# temperture.net
KiCad netlist of a schematic drawn in Altium Designer
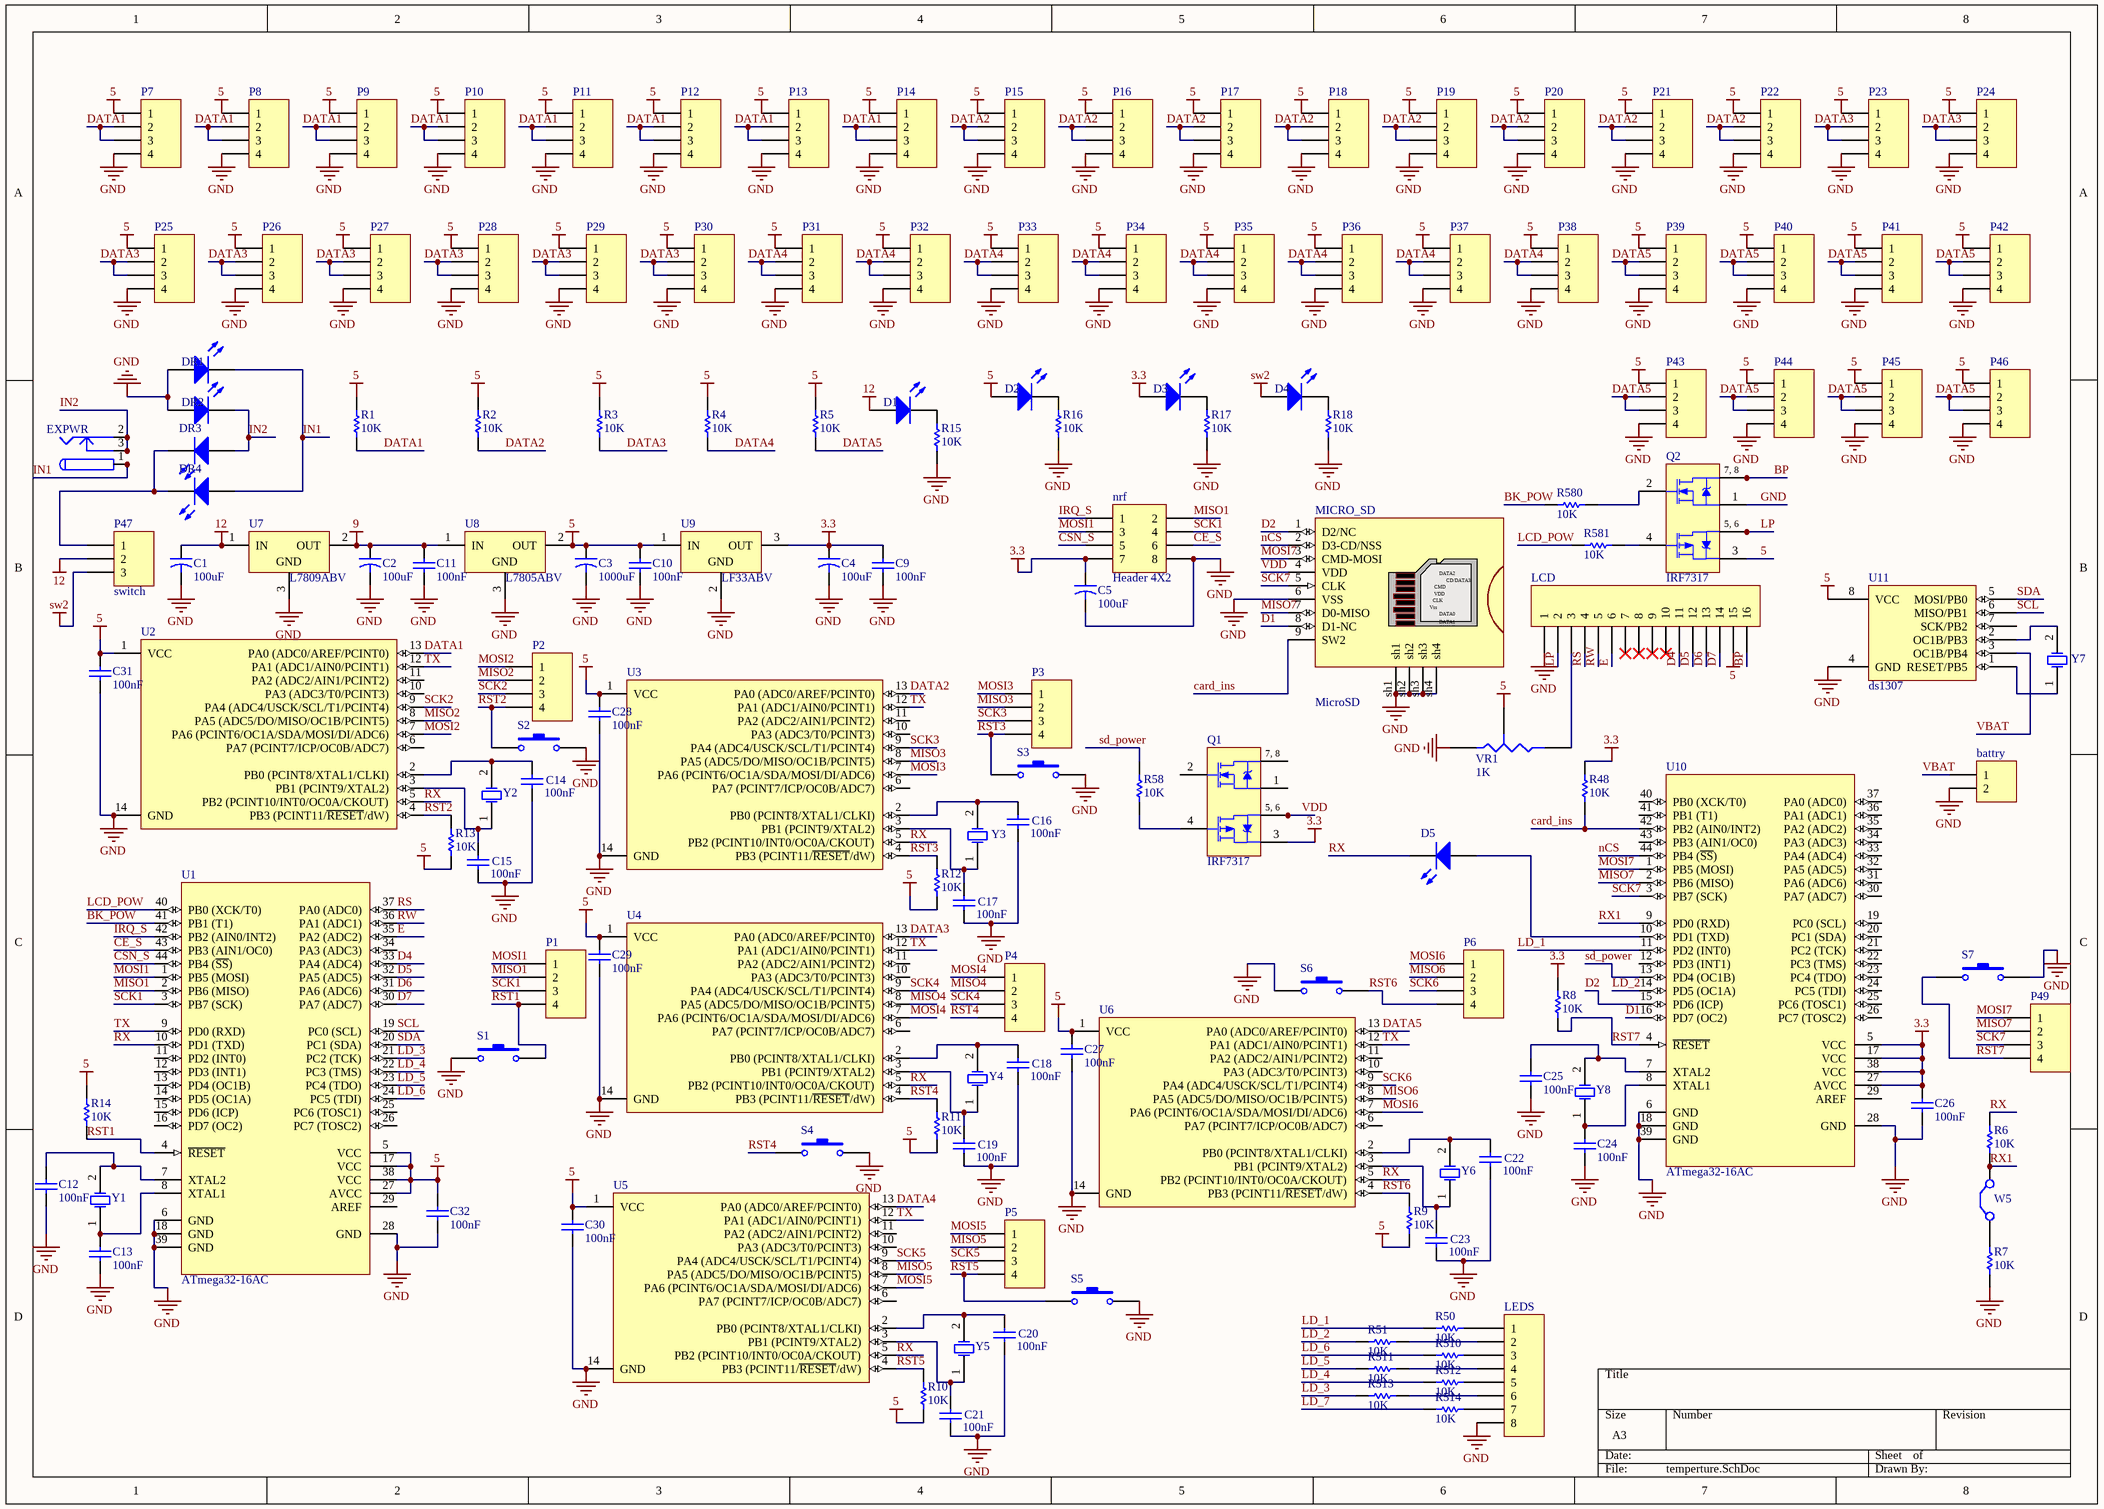
[diagram p0: temperture.SchDoc]

(export (version "E")
  (design (tool "Eeschema 10.0.6"))
  (components
    (comp (ref "battry")
      (value "Header 2")
      (footprint "Ultimate PCB Footprint:Battry")
      (description "Header, 2-Pin")
      (fields (field (name "PUBLISHER") "Altium Limited"))
      (libsource (lib "Miscellaneous Connectors") (part "Header 2"))
    )
    (comp (ref "C1")
      (value "100uF")
      (footprint "cap")
      (description "Capacitor")
      (fields (field (name "Comment") "Cap2") (field (name "PUBLISHER") "Altium Limited"))
      (libsource (lib "Miscellaneous Devices") (part "Cap2"))
    )
    (comp (ref "C2")
      (value "100uF")
      (footprint "cap")
      (description "Capacitor")
      (fields (field (name "Comment") "Cap2") (field (name "PUBLISHER") "Altium Limited"))
      (libsource (lib "Miscellaneous Devices") (part "Cap2"))
    )
    (comp (ref "C3")
      (value "1000uF")
      (footprint "cap")
      (description "Capacitor")
      (fields (field (name "Comment") "Cap2") (field (name "PUBLISHER") "Altium Limited"))
      (libsource (lib "Miscellaneous Devices") (part "Cap2"))
    )
    (comp (ref "C4")
      (value "100uF")
      (footprint "cap")
      (description "Capacitor")
      (fields (field (name "Comment") "Cap2") (field (name "PUBLISHER") "Altium Limited"))
      (libsource (lib "Miscellaneous Devices") (part "Cap2"))
    )
    (comp (ref "C5")
      (value "100uF")
      (footprint "cap")
      (description "Capacitor")
      (fields (field (name "Comment") "Cap2") (field (name "PUBLISHER") "Altium Limited"))
      (libsource (lib "Miscellaneous Devices") (part "Cap2"))
    )
    (comp (ref "C9")
      (value "100nF")
      (footprint "H1X02F")
      (description "Capacitor")
      (fields (field (name "Comment") "Cap") (field (name "PUBLISHER") "Altium Limited"))
      (libsource (lib "Miscellaneous Devices") (part "Cap"))
    )
    (comp (ref "C10")
      (value "100nF")
      (footprint "H1X02F")
      (description "Capacitor")
      (fields (field (name "Comment") "Cap") (field (name "PUBLISHER") "Altium Limited"))
      (libsource (lib "Miscellaneous Devices") (part "Cap"))
    )
    (comp (ref "C11")
      (value "100nF")
      (footprint "H1X02F")
      (description "Capacitor")
      (fields (field (name "Comment") "Cap") (field (name "PUBLISHER") "Altium Limited"))
      (libsource (lib "Miscellaneous Devices") (part "Cap"))
    )
    (comp (ref "C12")
      (value "100nF")
      (footprint "H1X02F")
      (description "Capacitor")
      (fields (field (name "Comment") "Cap") (field (name "PUBLISHER") "Altium Limited"))
      (libsource (lib "Miscellaneous Devices") (part "Cap"))
    )
    (comp (ref "C13")
      (value "100nF")
      (footprint "H1X02F")
      (description "Capacitor")
      (fields (field (name "Comment") "Cap") (field (name "PUBLISHER") "Altium Limited"))
      (libsource (lib "Miscellaneous Devices") (part "Cap"))
    )
    (comp (ref "C14")
      (value "100nF")
      (footprint "H1X02F")
      (description "Capacitor")
      (fields (field (name "Comment") "Cap") (field (name "PUBLISHER") "Altium Limited"))
      (libsource (lib "Miscellaneous Devices") (part "Cap"))
    )
    (comp (ref "C15")
      (value "100nF")
      (footprint "H1X02F")
      (description "Capacitor")
      (fields (field (name "Comment") "Cap") (field (name "PUBLISHER") "Altium Limited"))
      (libsource (lib "Miscellaneous Devices") (part "Cap"))
    )
    (comp (ref "C16")
      (value "100nF")
      (footprint "H1X02F")
      (description "Capacitor")
      (fields (field (name "Comment") "Cap") (field (name "PUBLISHER") "Altium Limited"))
      (libsource (lib "Miscellaneous Devices") (part "Cap"))
    )
    (comp (ref "C17")
      (value "100nF")
      (footprint "H1X02F")
      (description "Capacitor")
      (fields (field (name "Comment") "Cap") (field (name "PUBLISHER") "Altium Limited"))
      (libsource (lib "Miscellaneous Devices") (part "Cap"))
    )
    (comp (ref "C18")
      (value "100nF")
      (footprint "H1X02F")
      (description "Capacitor")
      (fields (field (name "Comment") "Cap") (field (name "PUBLISHER") "Altium Limited"))
      (libsource (lib "Miscellaneous Devices") (part "Cap"))
    )
    (comp (ref "C19")
      (value "100nF")
      (footprint "H1X02F")
      (description "Capacitor")
      (fields (field (name "Comment") "Cap") (field (name "PUBLISHER") "Altium Limited"))
      (libsource (lib "Miscellaneous Devices") (part "Cap"))
    )
    (comp (ref "C20")
      (value "100nF")
      (footprint "H1X02F")
      (description "Capacitor")
      (fields (field (name "Comment") "Cap") (field (name "PUBLISHER") "Altium Limited"))
      (libsource (lib "Miscellaneous Devices") (part "Cap"))
    )
    (comp (ref "C21")
      (value "100nF")
      (footprint "H1X02F")
      (description "Capacitor")
      (fields (field (name "Comment") "Cap") (field (name "PUBLISHER") "Altium Limited"))
      (libsource (lib "Miscellaneous Devices") (part "Cap"))
    )
    (comp (ref "C22")
      (value "100nF")
      (footprint "H1X02F")
      (description "Capacitor")
      (fields (field (name "Comment") "Cap") (field (name "PUBLISHER") "Altium Limited"))
      (libsource (lib "Miscellaneous Devices") (part "Cap"))
    )
    (comp (ref "C23")
      (value "100nF")
      (footprint "H1X02F")
      (description "Capacitor")
      (fields (field (name "Comment") "Cap") (field (name "PUBLISHER") "Altium Limited"))
      (libsource (lib "Miscellaneous Devices") (part "Cap"))
    )
    (comp (ref "C24")
      (value "100nF")
      (footprint "H1X02F")
      (description "Capacitor")
      (fields (field (name "Comment") "Cap") (field (name "PUBLISHER") "Altium Limited"))
      (libsource (lib "Miscellaneous Devices") (part "Cap"))
    )
    (comp (ref "C25")
      (value "100nF")
      (footprint "H1X02F")
      (description "Capacitor")
      (fields (field (name "Comment") "Cap") (field (name "PUBLISHER") "Altium Limited"))
      (libsource (lib "Miscellaneous Devices") (part "Cap"))
    )
    (comp (ref "C26")
      (value "100nF")
      (footprint "H1X02F")
      (description "Capacitor")
      (fields (field (name "Comment") "Cap") (field (name "PUBLISHER") "Altium Limited"))
      (libsource (lib "Miscellaneous Devices") (part "Cap"))
    )
    (comp (ref "C27")
      (value "100nF")
      (footprint "H1X02F")
      (description "Capacitor")
      (fields (field (name "Comment") "Cap") (field (name "PUBLISHER") "Altium Limited"))
      (libsource (lib "Miscellaneous Devices") (part "Cap"))
    )
    (comp (ref "C28")
      (value "100nF")
      (footprint "H1X02F")
      (description "Capacitor")
      (fields (field (name "Comment") "Cap") (field (name "PUBLISHER") "Altium Limited"))
      (libsource (lib "Miscellaneous Devices") (part "Cap"))
    )
    (comp (ref "C29")
      (value "100nF")
      (footprint "H1X02F")
      (description "Capacitor")
      (fields (field (name "Comment") "Cap") (field (name "PUBLISHER") "Altium Limited"))
      (libsource (lib "Miscellaneous Devices") (part "Cap"))
    )
    (comp (ref "C30")
      (value "100nF")
      (footprint "H1X02F")
      (description "Capacitor")
      (fields (field (name "Comment") "Cap") (field (name "PUBLISHER") "Altium Limited"))
      (libsource (lib "Miscellaneous Devices") (part "Cap"))
    )
    (comp (ref "C31")
      (value "100nF")
      (footprint "H1X02F")
      (description "Capacitor")
      (fields (field (name "Comment") "Cap") (field (name "PUBLISHER") "Altium Limited"))
      (libsource (lib "Miscellaneous Devices") (part "Cap"))
    )
    (comp (ref "C32")
      (value "100nF")
      (footprint "H1X02F")
      (description "Capacitor")
      (fields (field (name "Comment") "Cap") (field (name "PUBLISHER") "Altium Limited"))
      (libsource (lib "Miscellaneous Devices") (part "Cap"))
    )
    (comp (ref "D1")
      (value "LED0")
      (footprint "LED5mm")
      (description "Typical INFRARED GaAs LED")
      (fields (field (name "PUBLISHER") "Altium Limited"))
      (libsource (lib "Miscellaneous Devices") (part "LED0"))
    )
    (comp (ref "D2")
      (value "LED0")
      (footprint "LED5mm")
      (description "Typical INFRARED GaAs LED")
      (fields (field (name "PUBLISHER") "Altium Limited"))
      (libsource (lib "Miscellaneous Devices") (part "LED0"))
    )
    (comp (ref "D3")
      (value "LED0")
      (footprint "LED5mm")
      (description "Typical INFRARED GaAs LED")
      (fields (field (name "PUBLISHER") "Altium Limited"))
      (libsource (lib "Miscellaneous Devices") (part "LED0"))
    )
    (comp (ref "D4")
      (value "LED0")
      (footprint "LED5mm")
      (description "Typical INFRARED GaAs LED")
      (fields (field (name "PUBLISHER") "Altium Limited"))
      (libsource (lib "Miscellaneous Devices") (part "LED0"))
    )
    (comp (ref "D5")
      (value "LED0")
      (footprint "AXIAL-0.4")
      (description "Typical INFRARED GaAs LED")
      (fields (field (name "PUBLISHER") "Altium Limited"))
      (libsource (lib "Miscellaneous Devices") (part "LED0"))
    )
    (comp (ref "DR1")
      (value "LED0")
      (footprint "AXIAL-0.3")
      (description "Typical INFRARED GaAs LED")
      (fields (field (name "PUBLISHER") "Altium Limited"))
      (libsource (lib "Miscellaneous Devices") (part "LED0"))
    )
    (comp (ref "DR2")
      (value "LED0")
      (footprint "AXIAL-0.3")
      (description "Typical INFRARED GaAs LED")
      (fields (field (name "PUBLISHER") "Altium Limited"))
      (libsource (lib "Miscellaneous Devices") (part "LED0"))
    )
    (comp (ref "DR3")
      (value "LED0")
      (footprint "AXIAL-0.3")
      (description "Typical INFRARED GaAs LED")
      (fields (field (name "PUBLISHER") "Altium Limited"))
      (libsource (lib "Miscellaneous Devices") (part "LED0"))
    )
    (comp (ref "DR4")
      (value "LED0")
      (footprint "AXIAL-0.3")
      (description "Typical INFRARED GaAs LED")
      (fields (field (name "PUBLISHER") "Altium Limited"))
      (libsource (lib "Miscellaneous Devices") (part "LED0"))
    )
    (comp (ref "EXPWR")
      (value "PWR2.5")
      (footprint "JACK1")
      (description "Low Voltage Power Supply Connector")
      (fields (field (name "PUBLISHER") "Altium Limited"))
      (libsource (lib "Miscellaneous Connectors") (part "PWR2.5"))
    )
    (comp (ref "LCD")
      (value "Header 16")
      (footprint "H1X16F")
      (description "Header, 16-Pin")
      (fields (field (name "PUBLISHER") "Altium Limited"))
      (libsource (lib "Miscellaneous Connectors") (part "Header 16"))
    )
    (comp (ref "LEDS")
      (value "Header 8")
      (footprint "H1X08F")
      (description "Header, 8-Pin")
      (fields (field (name "PUBLISHER") "Altium Limited"))
      (libsource (lib "Miscellaneous Connectors") (part "Header 8"))
    )
    (comp (ref "MICRO_SD")
      (value "MicroSD")
      (footprint "MicroSD_1")
      (description "MicroSD_altium designer (M.Hariri)")
      (fields (field (name "CREATED BY:") "*"))
      (libsource (lib "MicroSD_altium designer") (part "MicroSD"))
    )
    (comp (ref "nrf")
      (value "Header 4X2")
      (footprint "HDR2X4")
      (description "Header, 4-Pin, Dual row")
      (fields (field (name "PUBLISHER") "Altium Limited"))
      (libsource (lib "Miscellaneous Connectors") (part "Header 4X2"))
    )
    (comp (ref "P1")
      (value "Header 4")
      (footprint "H1X04F")
      (description "Header, 4-Pin")
      (fields (field (name "PUBLISHER") "Altium Limited"))
      (libsource (lib "Miscellaneous Connectors") (part "Header 4"))
    )
    (comp (ref "P2")
      (value "Header 4")
      (footprint "H1X04F")
      (description "Header, 4-Pin")
      (fields (field (name "PUBLISHER") "Altium Limited"))
      (libsource (lib "Miscellaneous Connectors") (part "Header 4"))
    )
    (comp (ref "P3")
      (value "Header 4")
      (footprint "H1X04F")
      (description "Header, 4-Pin")
      (fields (field (name "PUBLISHER") "Altium Limited"))
      (libsource (lib "Miscellaneous Connectors") (part "Header 4"))
    )
    (comp (ref "P4")
      (value "Header 4")
      (footprint "H1X04F")
      (description "Header, 4-Pin")
      (fields (field (name "PUBLISHER") "Altium Limited"))
      (libsource (lib "Miscellaneous Connectors") (part "Header 4"))
    )
    (comp (ref "P5")
      (value "Header 4")
      (footprint "H1X04F")
      (description "Header, 4-Pin")
      (fields (field (name "PUBLISHER") "Altium Limited"))
      (libsource (lib "Miscellaneous Connectors") (part "Header 4"))
    )
    (comp (ref "P6")
      (value "Header 4")
      (footprint "H1X04F")
      (description "Header, 4-Pin")
      (fields (field (name "PUBLISHER") "Altium Limited"))
      (libsource (lib "Miscellaneous Connectors") (part "Header 4"))
    )
    (comp (ref "P7")
      (value "Header 4")
      (footprint "RJ11")
      (description "Header, 4-Pin")
      (fields (field (name "PUBLISHER") "Altium Limited"))
      (libsource (lib "Miscellaneous Connectors") (part "Header 4"))
    )
    (comp (ref "P8")
      (value "Header 4")
      (footprint "RJ11")
      (description "Header, 4-Pin")
      (fields (field (name "PUBLISHER") "Altium Limited"))
      (libsource (lib "Miscellaneous Connectors") (part "Header 4"))
    )
    (comp (ref "P9")
      (value "Header 4")
      (footprint "RJ11")
      (description "Header, 4-Pin")
      (fields (field (name "PUBLISHER") "Altium Limited"))
      (libsource (lib "Miscellaneous Connectors") (part "Header 4"))
    )
    (comp (ref "P10")
      (value "Header 4")
      (footprint "RJ11")
      (description "Header, 4-Pin")
      (fields (field (name "PUBLISHER") "Altium Limited"))
      (libsource (lib "Miscellaneous Connectors") (part "Header 4"))
    )
    (comp (ref "P11")
      (value "Header 4")
      (footprint "RJ11")
      (description "Header, 4-Pin")
      (fields (field (name "PUBLISHER") "Altium Limited"))
      (libsource (lib "Miscellaneous Connectors") (part "Header 4"))
    )
    (comp (ref "P12")
      (value "Header 4")
      (footprint "RJ11")
      (description "Header, 4-Pin")
      (fields (field (name "PUBLISHER") "Altium Limited"))
      (libsource (lib "Miscellaneous Connectors") (part "Header 4"))
    )
    (comp (ref "P13")
      (value "Header 4")
      (footprint "RJ11")
      (description "Header, 4-Pin")
      (fields (field (name "PUBLISHER") "Altium Limited"))
      (libsource (lib "Miscellaneous Connectors") (part "Header 4"))
    )
    (comp (ref "P14")
      (value "Header 4")
      (footprint "RJ11")
      (description "Header, 4-Pin")
      (fields (field (name "PUBLISHER") "Altium Limited"))
      (libsource (lib "Miscellaneous Connectors") (part "Header 4"))
    )
    (comp (ref "P15")
      (value "Header 4")
      (footprint "RJ11")
      (description "Header, 4-Pin")
      (fields (field (name "PUBLISHER") "Altium Limited"))
      (libsource (lib "Miscellaneous Connectors") (part "Header 4"))
    )
    (comp (ref "P16")
      (value "Header 4")
      (footprint "RJ11")
      (description "Header, 4-Pin")
      (fields (field (name "PUBLISHER") "Altium Limited"))
      (libsource (lib "Miscellaneous Connectors") (part "Header 4"))
    )
    (comp (ref "P17")
      (value "Header 4")
      (footprint "RJ11")
      (description "Header, 4-Pin")
      (fields (field (name "PUBLISHER") "Altium Limited"))
      (libsource (lib "Miscellaneous Connectors") (part "Header 4"))
    )
    (comp (ref "P18")
      (value "Header 4")
      (footprint "RJ11")
      (description "Header, 4-Pin")
      (fields (field (name "PUBLISHER") "Altium Limited"))
      (libsource (lib "Miscellaneous Connectors") (part "Header 4"))
    )
    (comp (ref "P19")
      (value "Header 4")
      (footprint "RJ11")
      (description "Header, 4-Pin")
      (fields (field (name "PUBLISHER") "Altium Limited"))
      (libsource (lib "Miscellaneous Connectors") (part "Header 4"))
    )
    (comp (ref "P20")
      (value "Header 4")
      (footprint "RJ11")
      (description "Header, 4-Pin")
      (fields (field (name "PUBLISHER") "Altium Limited"))
      (libsource (lib "Miscellaneous Connectors") (part "Header 4"))
    )
    (comp (ref "P21")
      (value "Header 4")
      (footprint "RJ11")
      (description "Header, 4-Pin")
      (fields (field (name "PUBLISHER") "Altium Limited"))
      (libsource (lib "Miscellaneous Connectors") (part "Header 4"))
    )
    (comp (ref "P22")
      (value "Header 4")
      (footprint "RJ11")
      (description "Header, 4-Pin")
      (fields (field (name "PUBLISHER") "Altium Limited"))
      (libsource (lib "Miscellaneous Connectors") (part "Header 4"))
    )
    (comp (ref "P23")
      (value "Header 4")
      (footprint "RJ11")
      (description "Header, 4-Pin")
      (fields (field (name "PUBLISHER") "Altium Limited"))
      (libsource (lib "Miscellaneous Connectors") (part "Header 4"))
    )
    (comp (ref "P24")
      (value "Header 4")
      (footprint "RJ11")
      (description "Header, 4-Pin")
      (fields (field (name "PUBLISHER") "Altium Limited"))
      (libsource (lib "Miscellaneous Connectors") (part "Header 4"))
    )
    (comp (ref "P25")
      (value "Header 4")
      (footprint "RJ11")
      (description "Header, 4-Pin")
      (fields (field (name "PUBLISHER") "Altium Limited"))
      (libsource (lib "Miscellaneous Connectors") (part "Header 4"))
    )
    (comp (ref "P26")
      (value "Header 4")
      (footprint "RJ11")
      (description "Header, 4-Pin")
      (fields (field (name "PUBLISHER") "Altium Limited"))
      (libsource (lib "Miscellaneous Connectors") (part "Header 4"))
    )
    (comp (ref "P27")
      (value "Header 4")
      (footprint "RJ11")
      (description "Header, 4-Pin")
      (fields (field (name "PUBLISHER") "Altium Limited"))
      (libsource (lib "Miscellaneous Connectors") (part "Header 4"))
    )
    (comp (ref "P28")
      (value "Header 4")
      (footprint "RJ11")
      (description "Header, 4-Pin")
      (fields (field (name "PUBLISHER") "Altium Limited"))
      (libsource (lib "Miscellaneous Connectors") (part "Header 4"))
    )
    (comp (ref "P29")
      (value "Header 4")
      (footprint "RJ11")
      (description "Header, 4-Pin")
      (fields (field (name "PUBLISHER") "Altium Limited"))
      (libsource (lib "Miscellaneous Connectors") (part "Header 4"))
    )
    (comp (ref "P30")
      (value "Header 4")
      (footprint "RJ11")
      (description "Header, 4-Pin")
      (fields (field (name "PUBLISHER") "Altium Limited"))
      (libsource (lib "Miscellaneous Connectors") (part "Header 4"))
    )
    (comp (ref "P31")
      (value "Header 4")
      (footprint "RJ11")
      (description "Header, 4-Pin")
      (fields (field (name "PUBLISHER") "Altium Limited"))
      (libsource (lib "Miscellaneous Connectors") (part "Header 4"))
    )
    (comp (ref "P32")
      (value "Header 4")
      (footprint "RJ11")
      (description "Header, 4-Pin")
      (fields (field (name "PUBLISHER") "Altium Limited"))
      (libsource (lib "Miscellaneous Connectors") (part "Header 4"))
    )
    (comp (ref "P33")
      (value "Header 4")
      (footprint "RJ11")
      (description "Header, 4-Pin")
      (fields (field (name "PUBLISHER") "Altium Limited"))
      (libsource (lib "Miscellaneous Connectors") (part "Header 4"))
    )
    (comp (ref "P34")
      (value "Header 4")
      (footprint "RJ11")
      (description "Header, 4-Pin")
      (fields (field (name "PUBLISHER") "Altium Limited"))
      (libsource (lib "Miscellaneous Connectors") (part "Header 4"))
    )
    (comp (ref "P35")
      (value "Header 4")
      (footprint "RJ11")
      (description "Header, 4-Pin")
      (fields (field (name "PUBLISHER") "Altium Limited"))
      (libsource (lib "Miscellaneous Connectors") (part "Header 4"))
    )
    (comp (ref "P36")
      (value "Header 4")
      (footprint "RJ11")
      (description "Header, 4-Pin")
      (fields (field (name "PUBLISHER") "Altium Limited"))
      (libsource (lib "Miscellaneous Connectors") (part "Header 4"))
    )
    (comp (ref "P37")
      (value "Header 4")
      (footprint "RJ11")
      (description "Header, 4-Pin")
      (fields (field (name "PUBLISHER") "Altium Limited"))
      (libsource (lib "Miscellaneous Connectors") (part "Header 4"))
    )
    (comp (ref "P38")
      (value "Header 4")
      (footprint "RJ11")
      (description "Header, 4-Pin")
      (fields (field (name "PUBLISHER") "Altium Limited"))
      (libsource (lib "Miscellaneous Connectors") (part "Header 4"))
    )
    (comp (ref "P39")
      (value "Header 4")
      (footprint "RJ11")
      (description "Header, 4-Pin")
      (fields (field (name "PUBLISHER") "Altium Limited"))
      (libsource (lib "Miscellaneous Connectors") (part "Header 4"))
    )
    (comp (ref "P40")
      (value "Header 4")
      (footprint "RJ11")
      (description "Header, 4-Pin")
      (fields (field (name "PUBLISHER") "Altium Limited"))
      (libsource (lib "Miscellaneous Connectors") (part "Header 4"))
    )
    (comp (ref "P41")
      (value "Header 4")
      (footprint "RJ11")
      (description "Header, 4-Pin")
      (fields (field (name "PUBLISHER") "Altium Limited"))
      (libsource (lib "Miscellaneous Connectors") (part "Header 4"))
    )
    (comp (ref "P42")
      (value "Header 4")
      (footprint "RJ11")
      (description "Header, 4-Pin")
      (fields (field (name "PUBLISHER") "Altium Limited"))
      (libsource (lib "Miscellaneous Connectors") (part "Header 4"))
    )
    (comp (ref "P43")
      (value "Header 4")
      (footprint "RJ11")
      (description "Header, 4-Pin")
      (fields (field (name "PUBLISHER") "Altium Limited"))
      (libsource (lib "Miscellaneous Connectors") (part "Header 4"))
    )
    (comp (ref "P44")
      (value "Header 4")
      (footprint "RJ11")
      (description "Header, 4-Pin")
      (fields (field (name "PUBLISHER") "Altium Limited"))
      (libsource (lib "Miscellaneous Connectors") (part "Header 4"))
    )
    (comp (ref "P45")
      (value "Header 4")
      (footprint "RJ11")
      (description "Header, 4-Pin")
      (fields (field (name "PUBLISHER") "Altium Limited"))
      (libsource (lib "Miscellaneous Connectors") (part "Header 4"))
    )
    (comp (ref "P46")
      (value "Header 4")
      (footprint "RJ11")
      (description "Header, 4-Pin")
      (fields (field (name "PUBLISHER") "Altium Limited"))
      (libsource (lib "Miscellaneous Connectors") (part "Header 4"))
    )
    (comp (ref "P47")
      (value "switch")
      (footprint "peymanswitch")
      (description "Header, 3-Pin")
      (fields (field (name "PUBLISHER") "Altium Limited"))
      (libsource (lib "Miscellaneous Connectors") (part "Header 3"))
    )
    (comp (ref "P49")
      (value "Header 4")
      (footprint "H1X04F")
      (description "Header, 4-Pin")
      (fields (field (name "PUBLISHER") "Altium Limited"))
      (libsource (lib "Miscellaneous Connectors") (part "Header 4"))
    )
    (comp (ref "Q1")
      (value "IRF7317")
      (footprint "SO-8_N")
      (description "HEXFET Power MOSFET")
      (fields (field (name "PUBLISHER") "Altium Limited"))
      (libsource (lib "IR Discrete MOSFET - Power") (part "IRF7317"))
    )
    (comp (ref "Q2")
      (value "IRF7317")
      (footprint "International Rectifier Footprints:SO-8_N")
      (description "HEXFET Power MOSFET")
      (fields (field (name "PUBLISHER") "Altium Limited"))
      (libsource (lib "IR Discrete MOSFET - Power") (part "IRF7317"))
    )
    (comp (ref "R1")
      (value "10K")
      (footprint "AXIAL-0.3")
      (description "Resistor")
      (fields (field (name "Comment") "Res1") (field (name "PUBLISHER") "Altium Limited"))
      (libsource (lib "Miscellaneous Devices") (part "Res1"))
    )
    (comp (ref "R2")
      (value "10K")
      (footprint "AXIAL-0.3")
      (description "Resistor")
      (fields (field (name "Comment") "Res1") (field (name "PUBLISHER") "Altium Limited"))
      (libsource (lib "Miscellaneous Devices") (part "Res1"))
    )
    (comp (ref "R3")
      (value "10K")
      (footprint "AXIAL-0.3")
      (description "Resistor")
      (fields (field (name "Comment") "Res1") (field (name "PUBLISHER") "Altium Limited"))
      (libsource (lib "Miscellaneous Devices") (part "Res1"))
    )
    (comp (ref "R4")
      (value "10K")
      (footprint "AXIAL-0.3")
      (description "Resistor")
      (fields (field (name "Comment") "Res1") (field (name "PUBLISHER") "Altium Limited"))
      (libsource (lib "Miscellaneous Devices") (part "Res1"))
    )
    (comp (ref "R5")
      (value "10K")
      (footprint "AXIAL-0.3")
      (description "Resistor")
      (fields (field (name "Comment") "Res1") (field (name "PUBLISHER") "Altium Limited"))
      (libsource (lib "Miscellaneous Devices") (part "Res1"))
    )
    (comp (ref "R6")
      (value "10K")
      (footprint "AXIAL-0.3")
      (description "Resistor")
      (fields (field (name "Comment") "Res1") (field (name "PUBLISHER") "Altium Limited"))
      (libsource (lib "Miscellaneous Devices") (part "Res1"))
    )
    (comp (ref "R7")
      (value "10K")
      (footprint "AXIAL-0.3")
      (description "Resistor")
      (fields (field (name "Comment") "Res1") (field (name "PUBLISHER") "Altium Limited"))
      (libsource (lib "Miscellaneous Devices") (part "Res1"))
    )
    (comp (ref "R8")
      (value "10K")
      (footprint "AXIAL-0.3")
      (description "Resistor")
      (fields (field (name "Comment") "Res1") (field (name "PUBLISHER") "Altium Limited"))
      (libsource (lib "Miscellaneous Devices") (part "Res1"))
    )
    (comp (ref "R9")
      (value "10K")
      (footprint "AXIAL-0.3")
      (description "Resistor")
      (fields (field (name "Comment") "Res1") (field (name "PUBLISHER") "Altium Limited"))
      (libsource (lib "Miscellaneous Devices") (part "Res1"))
    )
    (comp (ref "R10")
      (value "10K")
      (footprint "AXIAL-0.3")
      (description "Resistor")
      (fields (field (name "Comment") "Res1") (field (name "PUBLISHER") "Altium Limited"))
      (libsource (lib "Miscellaneous Devices") (part "Res1"))
    )
    (comp (ref "R11")
      (value "10K")
      (footprint "AXIAL-0.3")
      (description "Resistor")
      (fields (field (name "Comment") "Res1") (field (name "PUBLISHER") "Altium Limited"))
      (libsource (lib "Miscellaneous Devices") (part "Res1"))
    )
    (comp (ref "R12")
      (value "10K")
      (footprint "AXIAL-0.3")
      (description "Resistor")
      (fields (field (name "Comment") "Res1") (field (name "PUBLISHER") "Altium Limited"))
      (libsource (lib "Miscellaneous Devices") (part "Res1"))
    )
    (comp (ref "R13")
      (value "10K")
      (footprint "AXIAL-0.3")
      (description "Resistor")
      (fields (field (name "Comment") "Res1") (field (name "PUBLISHER") "Altium Limited"))
      (libsource (lib "Miscellaneous Devices") (part "Res1"))
    )
    (comp (ref "R14")
      (value "10K")
      (footprint "AXIAL-0.3")
      (description "Resistor")
      (fields (field (name "Comment") "Res1") (field (name "PUBLISHER") "Altium Limited"))
      (libsource (lib "Miscellaneous Devices") (part "Res1"))
    )
    (comp (ref "R15")
      (value "10K")
      (footprint "AXIAL-0.3")
      (description "Resistor")
      (fields (field (name "Comment") "Res1") (field (name "PUBLISHER") "Altium Limited"))
      (libsource (lib "Miscellaneous Devices") (part "Res1"))
    )
    (comp (ref "R16")
      (value "10K")
      (footprint "AXIAL-0.3")
      (description "Resistor")
      (fields (field (name "Comment") "Res1") (field (name "PUBLISHER") "Altium Limited"))
      (libsource (lib "Miscellaneous Devices") (part "Res1"))
    )
    (comp (ref "R17")
      (value "10K")
      (footprint "AXIAL-0.3")
      (description "Resistor")
      (fields (field (name "Comment") "Res1") (field (name "PUBLISHER") "Altium Limited"))
      (libsource (lib "Miscellaneous Devices") (part "Res1"))
    )
    (comp (ref "R18")
      (value "10K")
      (footprint "AXIAL-0.3")
      (description "Resistor")
      (fields (field (name "Comment") "Res1") (field (name "PUBLISHER") "Altium Limited"))
      (libsource (lib "Miscellaneous Devices") (part "Res1"))
    )
    (comp (ref "R48")
      (value "10K")
      (footprint "AXIAL-0.3")
      (description "Resistor")
      (fields (field (name "Comment") "Res1") (field (name "PUBLISHER") "Altium Limited"))
      (libsource (lib "Miscellaneous Devices") (part "Res1"))
    )
    (comp (ref "R50")
      (value "10K")
      (footprint "AXIAL-0.3")
      (description "Resistor")
      (fields (field (name "Comment") "Res1") (field (name "PUBLISHER") "Altium Limited"))
      (libsource (lib "Miscellaneous Devices") (part "Res1"))
    )
    (comp (ref "R51")
      (value "10K")
      (footprint "AXIAL-0.3")
      (description "Resistor")
      (fields (field (name "Comment") "Res1") (field (name "PUBLISHER") "Altium Limited"))
      (libsource (lib "Miscellaneous Devices") (part "Res1"))
    )
    (comp (ref "R58")
      (value "10K")
      (footprint "AXIAL-0.3")
      (description "Resistor")
      (fields (field (name "Comment") "Res1") (field (name "PUBLISHER") "Altium Limited"))
      (libsource (lib "Miscellaneous Devices") (part "Res1"))
    )
    (comp (ref "R510")
      (value "10K")
      (footprint "SMD[1206]")
      (description "Resistor")
      (fields (field (name "Comment") "Res1") (field (name "PUBLISHER") "Altium Limited"))
      (libsource (lib "Miscellaneous Devices") (part "Res1"))
    )
    (comp (ref "R511")
      (value "10K")
      (footprint "SMD[1206]")
      (description "Resistor")
      (fields (field (name "Comment") "Res1") (field (name "PUBLISHER") "Altium Limited"))
      (libsource (lib "Miscellaneous Devices") (part "Res1"))
    )
    (comp (ref "R512")
      (value "10K")
      (footprint "SMD[1206]")
      (description "Resistor")
      (fields (field (name "Comment") "Res1") (field (name "PUBLISHER") "Altium Limited"))
      (libsource (lib "Miscellaneous Devices") (part "Res1"))
    )
    (comp (ref "R513")
      (value "10K")
      (footprint "SMD[1206]")
      (description "Resistor")
      (fields (field (name "Comment") "Res1") (field (name "PUBLISHER") "Altium Limited"))
      (libsource (lib "Miscellaneous Devices") (part "Res1"))
    )
    (comp (ref "R514")
      (value "10K")
      (footprint "SMD[1206]")
      (description "Resistor")
      (fields (field (name "Comment") "Res1") (field (name "PUBLISHER") "Altium Limited"))
      (libsource (lib "Miscellaneous Devices") (part "Res1"))
    )
    (comp (ref "R580")
      (value "10K")
      (footprint "AXIAL-0.3")
      (description "Resistor")
      (fields (field (name "Comment") "Res1") (field (name "PUBLISHER") "Altium Limited"))
      (libsource (lib "Miscellaneous Devices") (part "Res1"))
    )
    (comp (ref "R581")
      (value "10K")
      (footprint "AXIAL-0.3")
      (description "Resistor")
      (fields (field (name "Comment") "Res1") (field (name "PUBLISHER") "Altium Limited"))
      (libsource (lib "Miscellaneous Devices") (part "Res1"))
    )
    (comp (ref "S1")
      (value "SW-PB")
      (footprint "PB4")
      (description "Switch")
      (fields (field (name "PUBLISHER") "Altium Limited"))
      (libsource (lib "Miscellaneous Devices") (part "SW-PB"))
    )
    (comp (ref "S2")
      (value "SW-PB")
      (footprint "PB4")
      (description "Switch")
      (fields (field (name "PUBLISHER") "Altium Limited"))
      (libsource (lib "Miscellaneous Devices") (part "SW-PB"))
    )
    (comp (ref "S3")
      (value "SW-PB")
      (footprint "PB4")
      (description "Switch")
      (fields (field (name "PUBLISHER") "Altium Limited"))
      (libsource (lib "Miscellaneous Devices") (part "SW-PB"))
    )
    (comp (ref "S4")
      (value "SW-PB")
      (footprint "PB4")
      (description "Switch")
      (fields (field (name "PUBLISHER") "Altium Limited"))
      (libsource (lib "Miscellaneous Devices") (part "SW-PB"))
    )
    (comp (ref "S5")
      (value "SW-PB")
      (footprint "PB4")
      (description "Switch")
      (fields (field (name "PUBLISHER") "Altium Limited"))
      (libsource (lib "Miscellaneous Devices") (part "SW-PB"))
    )
    (comp (ref "S6")
      (value "SW-PB")
      (footprint "PB4")
      (description "Switch")
      (fields (field (name "PUBLISHER") "Altium Limited"))
      (libsource (lib "Miscellaneous Devices") (part "SW-PB"))
    )
    (comp (ref "S7")
      (value "SW-PB")
      (footprint "PB4")
      (description "Switch")
      (fields (field (name "PUBLISHER") "Altium Limited"))
      (libsource (lib "Miscellaneous Devices") (part "SW-PB"))
    )
    (comp (ref "U1")
      (value "ATmega32-16AC")
      (footprint "TQFP44")
      (description "8-Bit AVR Microcontroller with 32K Bytes of In-System Programmable Flash Memory")
      (fields (field (name "PUBLISHER") "Altium Limited"))
      (libsource (lib "Atmel Microcontroller 8-Bit AVR") (part "ATmega32-16AC"))
    )
    (comp (ref "U2")
      (value "ATtiny24V-10SSU")
      (footprint "SOIC14")
      (fields (field (name "PUBLISHER") "Altium Limited"))
      (libsource (lib "Atmel Microcontroller 8-Bit tinyAVR") (part "ATtiny24V-10SSU"))
    )
    (comp (ref "U3")
      (value "ATtiny24V-10SSU")
      (footprint "SOIC14")
      (fields (field (name "PUBLISHER") "Altium Limited"))
      (libsource (lib "Atmel Microcontroller 8-Bit tinyAVR") (part "ATtiny24V-10SSU"))
    )
    (comp (ref "U4")
      (value "ATtiny24V-10SSU")
      (footprint "SOIC14")
      (fields (field (name "PUBLISHER") "Altium Limited"))
      (libsource (lib "Atmel Microcontroller 8-Bit tinyAVR") (part "ATtiny24V-10SSU"))
    )
    (comp (ref "U5")
      (value "ATtiny24V-10SSU")
      (footprint "SOIC14")
      (fields (field (name "PUBLISHER") "Altium Limited"))
      (libsource (lib "Atmel Microcontroller 8-Bit tinyAVR") (part "ATtiny24V-10SSU"))
    )
    (comp (ref "U6")
      (value "ATtiny24V-10SSU")
      (footprint "SOIC14")
      (fields (field (name "PUBLISHER") "Altium Limited"))
      (libsource (lib "Atmel Microcontroller 8-Bit tinyAVR") (part "ATtiny24V-10SSU"))
    )
    (comp (ref "U7")
      (value "L7809ABV")
      (footprint "TO220ABN")
      (description "Precision 1A Regulator")
      (fields (field (name "PUBLISHER") "Altium Limited"))
      (libsource (lib "ST Power Mgt Voltage Regulator") (part "L7809ABV"))
    )
    (comp (ref "U8")
      (value "L7805ABV")
      (footprint "TO220ABN")
      (description "Precision 1A Regulator")
      (fields (field (name "PUBLISHER") "Altium Limited"))
      (libsource (lib "ST Power Mgt Voltage Regulator") (part "L7805ABV"))
    )
    (comp (ref "U9")
      (value "LF33ABV")
      (footprint "TO-220A")
      (description "500mA, Very Low Drop (0.45V) Voltage Regulator")
      (fields (field (name "PUBLISHER") "Altium Limited"))
      (libsource (lib "ST Power Mgt Voltage Regulator") (part "LF33ABV"))
    )
    (comp (ref "U10")
      (value "ATmega32-16AC")
      (footprint "TQFP44")
      (description "8-Bit AVR Microcontroller with 32K Bytes of In-System Programmable Flash Memory")
      (fields (field (name "PUBLISHER") "Altium Limited"))
      (libsource (lib "Atmel Microcontroller 8-Bit AVR") (part "ATmega32-16AC"))
    )
    (comp (ref "U11")
      (value "ds1307")
      (footprint "DIP8-1")
      (description "Attiny45")
      (libsource (lib "Attiny85") (part "Attiny85"))
    )
    (comp (ref "VR1")
      (value "1K")
      (footprint "H1X03F")
      (description "Tapped Resistor")
      (fields (field (name "Comment") "Res Tap") (field (name "PUBLISHER") "Altium Limited"))
      (libsource (lib "Miscellaneous Devices") (part "Res Tap"))
    )
    (comp (ref "W5")
      (value "Jumper")
      (footprint "H1X02F")
      (description "Jumper Wire")
      (fields (field (name "PUBLISHER") "Altium Limited"))
      (libsource (lib "Miscellaneous Devices") (part "Jumper"))
    )
    (comp (ref "Y1")
      (value "XTAL")
      (footprint "CRYSTALL")
      (description "Crystal Oscillator")
      (fields (field (name "PUBLISHER") "Altium Limited"))
      (libsource (lib "Miscellaneous Devices") (part "XTAL"))
    )
    (comp (ref "Y2")
      (value "XTAL")
      (footprint "CRYSTALL")
      (description "Crystal Oscillator")
      (fields (field (name "PUBLISHER") "Altium Limited"))
      (libsource (lib "Miscellaneous Devices") (part "XTAL"))
    )
    (comp (ref "Y3")
      (value "XTAL")
      (footprint "CRYSTALL")
      (description "Crystal Oscillator")
      (fields (field (name "PUBLISHER") "Altium Limited"))
      (libsource (lib "Miscellaneous Devices") (part "XTAL"))
    )
    (comp (ref "Y4")
      (value "XTAL")
      (footprint "CRYSTALL")
      (description "Crystal Oscillator")
      (fields (field (name "PUBLISHER") "Altium Limited"))
      (libsource (lib "Miscellaneous Devices") (part "XTAL"))
    )
    (comp (ref "Y5")
      (value "XTAL")
      (footprint "CRYSTALL")
      (description "Crystal Oscillator")
      (fields (field (name "PUBLISHER") "Altium Limited"))
      (libsource (lib "Miscellaneous Devices") (part "XTAL"))
    )
    (comp (ref "Y6")
      (value "XTAL")
      (footprint "CRYSTALL")
      (description "Crystal Oscillator")
      (fields (field (name "PUBLISHER") "Altium Limited"))
      (libsource (lib "Miscellaneous Devices") (part "XTAL"))
    )
    (comp (ref "Y7")
      (value "XTAL")
      (footprint "H1X02F")
      (description "Crystal Oscillator")
      (fields (field (name "PUBLISHER") "Altium Limited"))
      (libsource (lib "Miscellaneous Devices") (part "XTAL"))
    )
    (comp (ref "Y8")
      (value "XTAL")
      (footprint "CRYSTALL")
      (description "Crystal Oscillator")
      (fields (field (name "PUBLISHER") "Altium Limited"))
      (libsource (lib "Miscellaneous Devices") (part "XTAL"))
    )
  )
  (nets
    (net (code "1") (name "/BK_POW") (class "Default")
      (node (ref "R580") (pin "1") (pinfunction "1_1") (pintype "passive"))
      (node (ref "U1") (pin "41") (pinfunction "PB1_(T1)_41") (pintype "bidirectional"))
    )
    (net (code "2") (name "/BP") (class "Default")
      (node (ref "LCD") (pin "16") (pinfunction "16_16") (pintype "passive"))
      (node (ref "Q2") (pin "7") (pinfunction "D1_7") (pintype "passive"))
      (node (ref "Q2") (pin "8") (pinfunction "D1_8") (pintype "passive"))
    )
    (net (code "3") (name "/CE_S") (class "Default")
      (node (ref "U1") (pin "43") (pinfunction "PB3_(AIN1/OC0)_43") (pintype "bidirectional"))
      (node (ref "nrf") (pin "6") (pinfunction "6_6") (pintype "passive"))
    )
    (net (code "4") (name "/CSN_S") (class "Default")
      (node (ref "U1") (pin "44") (pinfunction "PB4_(~{SS})_44") (pintype "bidirectional"))
      (node (ref "nrf") (pin "5") (pinfunction "5_5") (pintype "passive"))
    )
    (net (code "5") (name "/D1") (class "Default")
      (node (ref "MICRO_SD") (pin "8") (pinfunction "D1-NC_8") (pintype "bidirectional"))
      (node (ref "U10") (pin "16") (pinfunction "PD7_(OC2)_16") (pintype "bidirectional"))
    )
    (net (code "6") (name "/D2") (class "Default")
      (node (ref "MICRO_SD") (pin "1") (pinfunction "D2/NC_1") (pintype "bidirectional"))
      (node (ref "U10") (pin "15") (pinfunction "PD6_(ICP)_15") (pintype "bidirectional"))
    )
    (net (code "7") (name "/D4") (class "Default")
      (node (ref "LCD") (pin "11") (pinfunction "11_11") (pintype "passive"))
      (node (ref "U1") (pin "33") (pinfunction "PA4_(ADC4)_33") (pintype "bidirectional"))
    )
    (net (code "8") (name "/D5") (class "Default")
      (node (ref "LCD") (pin "12") (pinfunction "12_12") (pintype "passive"))
      (node (ref "U1") (pin "32") (pinfunction "PA5_(ADC5)_32") (pintype "bidirectional"))
    )
    (net (code "9") (name "/D6") (class "Default")
      (node (ref "LCD") (pin "13") (pinfunction "13_13") (pintype "passive"))
      (node (ref "U1") (pin "31") (pinfunction "PA6_(ADC6)_31") (pintype "bidirectional"))
    )
    (net (code "10") (name "/D7") (class "Default")
      (node (ref "LCD") (pin "14") (pinfunction "14_14") (pintype "passive"))
      (node (ref "U1") (pin "30") (pinfunction "PA7_(ADC7)_30") (pintype "bidirectional"))
    )
    (net (code "11") (name "/DATA1") (class "Default")
      (node (ref "P10") (pin "2") (pinfunction "2_2") (pintype "passive"))
      (node (ref "P10") (pin "3") (pinfunction "3_3") (pintype "passive"))
      (node (ref "P11") (pin "2") (pinfunction "2_2") (pintype "passive"))
      (node (ref "P11") (pin "3") (pinfunction "3_3") (pintype "passive"))
      (node (ref "P12") (pin "2") (pinfunction "2_2") (pintype "passive"))
      (node (ref "P12") (pin "3") (pinfunction "3_3") (pintype "passive"))
      (node (ref "P13") (pin "2") (pinfunction "2_2") (pintype "passive"))
      (node (ref "P13") (pin "3") (pinfunction "3_3") (pintype "passive"))
      (node (ref "P14") (pin "2") (pinfunction "2_2") (pintype "passive"))
      (node (ref "P14") (pin "3") (pinfunction "3_3") (pintype "passive"))
      (node (ref "P7") (pin "2") (pinfunction "2_2") (pintype "passive"))
      (node (ref "P7") (pin "3") (pinfunction "3_3") (pintype "passive"))
      (node (ref "P8") (pin "2") (pinfunction "2_2") (pintype "passive"))
      (node (ref "P8") (pin "3") (pinfunction "3_3") (pintype "passive"))
      (node (ref "P9") (pin "2") (pinfunction "2_2") (pintype "passive"))
      (node (ref "P9") (pin "3") (pinfunction "3_3") (pintype "passive"))
      (node (ref "R1") (pin "1") (pinfunction "1_1") (pintype "passive"))
      (node (ref "U2") (pin "13") (pinfunction "PA0_(ADC0/AREF/PCINT0)_13") (pintype "bidirectional"))
    )
    (net (code "12") (name "/DATA2") (class "Default")
      (node (ref "P15") (pin "2") (pinfunction "2_2") (pintype "passive"))
      (node (ref "P15") (pin "3") (pinfunction "3_3") (pintype "passive"))
      (node (ref "P16") (pin "2") (pinfunction "2_2") (pintype "passive"))
      (node (ref "P16") (pin "3") (pinfunction "3_3") (pintype "passive"))
      (node (ref "P17") (pin "2") (pinfunction "2_2") (pintype "passive"))
      (node (ref "P17") (pin "3") (pinfunction "3_3") (pintype "passive"))
      (node (ref "P18") (pin "2") (pinfunction "2_2") (pintype "passive"))
      (node (ref "P18") (pin "3") (pinfunction "3_3") (pintype "passive"))
      (node (ref "P19") (pin "2") (pinfunction "2_2") (pintype "passive"))
      (node (ref "P19") (pin "3") (pinfunction "3_3") (pintype "passive"))
      (node (ref "P20") (pin "2") (pinfunction "2_2") (pintype "passive"))
      (node (ref "P20") (pin "3") (pinfunction "3_3") (pintype "passive"))
      (node (ref "P21") (pin "2") (pinfunction "2_2") (pintype "passive"))
      (node (ref "P21") (pin "3") (pinfunction "3_3") (pintype "passive"))
      (node (ref "P22") (pin "2") (pinfunction "2_2") (pintype "passive"))
      (node (ref "P22") (pin "3") (pinfunction "3_3") (pintype "passive"))
      (node (ref "R2") (pin "1") (pinfunction "1_1") (pintype "passive"))
      (node (ref "U3") (pin "13") (pinfunction "PA0_(ADC0/AREF/PCINT0)_13") (pintype "bidirectional"))
    )
    (net (code "13") (name "/DATA3") (class "Default")
      (node (ref "P23") (pin "2") (pinfunction "2_2") (pintype "passive"))
      (node (ref "P23") (pin "3") (pinfunction "3_3") (pintype "passive"))
      (node (ref "P24") (pin "2") (pinfunction "2_2") (pintype "passive"))
      (node (ref "P24") (pin "3") (pinfunction "3_3") (pintype "passive"))
      (node (ref "P25") (pin "2") (pinfunction "2_2") (pintype "passive"))
      (node (ref "P25") (pin "3") (pinfunction "3_3") (pintype "passive"))
      (node (ref "P26") (pin "2") (pinfunction "2_2") (pintype "passive"))
      (node (ref "P26") (pin "3") (pinfunction "3_3") (pintype "passive"))
      (node (ref "P27") (pin "2") (pinfunction "2_2") (pintype "passive"))
      (node (ref "P27") (pin "3") (pinfunction "3_3") (pintype "passive"))
      (node (ref "P28") (pin "2") (pinfunction "2_2") (pintype "passive"))
      (node (ref "P28") (pin "3") (pinfunction "3_3") (pintype "passive"))
      (node (ref "P29") (pin "2") (pinfunction "2_2") (pintype "passive"))
      (node (ref "P29") (pin "3") (pinfunction "3_3") (pintype "passive"))
      (node (ref "P30") (pin "2") (pinfunction "2_2") (pintype "passive"))
      (node (ref "P30") (pin "3") (pinfunction "3_3") (pintype "passive"))
      (node (ref "R3") (pin "1") (pinfunction "1_1") (pintype "passive"))
      (node (ref "U4") (pin "13") (pinfunction "PA0_(ADC0/AREF/PCINT0)_13") (pintype "bidirectional"))
    )
    (net (code "14") (name "/DATA4") (class "Default")
      (node (ref "P31") (pin "2") (pinfunction "2_2") (pintype "passive"))
      (node (ref "P31") (pin "3") (pinfunction "3_3") (pintype "passive"))
      (node (ref "P32") (pin "2") (pinfunction "2_2") (pintype "passive"))
      (node (ref "P32") (pin "3") (pinfunction "3_3") (pintype "passive"))
      (node (ref "P33") (pin "2") (pinfunction "2_2") (pintype "passive"))
      (node (ref "P33") (pin "3") (pinfunction "3_3") (pintype "passive"))
      (node (ref "P34") (pin "2") (pinfunction "2_2") (pintype "passive"))
      (node (ref "P34") (pin "3") (pinfunction "3_3") (pintype "passive"))
      (node (ref "P35") (pin "2") (pinfunction "2_2") (pintype "passive"))
      (node (ref "P35") (pin "3") (pinfunction "3_3") (pintype "passive"))
      (node (ref "P36") (pin "2") (pinfunction "2_2") (pintype "passive"))
      (node (ref "P36") (pin "3") (pinfunction "3_3") (pintype "passive"))
      (node (ref "P37") (pin "2") (pinfunction "2_2") (pintype "passive"))
      (node (ref "P37") (pin "3") (pinfunction "3_3") (pintype "passive"))
      (node (ref "P38") (pin "2") (pinfunction "2_2") (pintype "passive"))
      (node (ref "P38") (pin "3") (pinfunction "3_3") (pintype "passive"))
      (node (ref "R4") (pin "1") (pinfunction "1_1") (pintype "passive"))
      (node (ref "U5") (pin "13") (pinfunction "PA0_(ADC0/AREF/PCINT0)_13") (pintype "bidirectional"))
    )
    (net (code "15") (name "/DATA5") (class "Default")
      (node (ref "P39") (pin "2") (pinfunction "2_2") (pintype "passive"))
      (node (ref "P39") (pin "3") (pinfunction "3_3") (pintype "passive"))
      (node (ref "P40") (pin "2") (pinfunction "2_2") (pintype "passive"))
      (node (ref "P40") (pin "3") (pinfunction "3_3") (pintype "passive"))
      (node (ref "P41") (pin "2") (pinfunction "2_2") (pintype "passive"))
      (node (ref "P41") (pin "3") (pinfunction "3_3") (pintype "passive"))
      (node (ref "P42") (pin "2") (pinfunction "2_2") (pintype "passive"))
      (node (ref "P42") (pin "3") (pinfunction "3_3") (pintype "passive"))
      (node (ref "P43") (pin "2") (pinfunction "2_2") (pintype "passive"))
      (node (ref "P43") (pin "3") (pinfunction "3_3") (pintype "passive"))
      (node (ref "P44") (pin "2") (pinfunction "2_2") (pintype "passive"))
      (node (ref "P44") (pin "3") (pinfunction "3_3") (pintype "passive"))
      (node (ref "P45") (pin "2") (pinfunction "2_2") (pintype "passive"))
      (node (ref "P45") (pin "3") (pinfunction "3_3") (pintype "passive"))
      (node (ref "P46") (pin "2") (pinfunction "2_2") (pintype "passive"))
      (node (ref "P46") (pin "3") (pinfunction "3_3") (pintype "passive"))
      (node (ref "R5") (pin "1") (pinfunction "1_1") (pintype "passive"))
      (node (ref "U6") (pin "13") (pinfunction "PA0_(ADC0/AREF/PCINT0)_13") (pintype "bidirectional"))
    )
    (net (code "16") (name "/E") (class "Default")
      (node (ref "LCD") (pin "6") (pinfunction "6_6") (pintype "passive"))
      (node (ref "U1") (pin "35") (pinfunction "PA2_(ADC2)_35") (pintype "bidirectional"))
    )
    (net (code "17") (name "/IN1") (class "Default")
      (node (ref "DR1") (pin "2") (pinfunction "K_2") (pintype "passive"))
      (node (ref "DR4") (pin "1") (pinfunction "A_1") (pintype "passive"))
      (node (ref "EXPWR") (pin "1") (pinfunction "1_1") (pintype "power_in"))
      (node (ref "EXPWR") (pin "1A") (pinfunction "1A_1A") (pintype "power_in"))
      (node (ref "EXPWR") (pin "1B") (pinfunction "1B_1B") (pintype "power_in"))
    )
    (net (code "18") (name "/IN2") (class "Default")
      (node (ref "DR2") (pin "2") (pinfunction "K_2") (pintype "passive"))
      (node (ref "DR3") (pin "1") (pinfunction "A_1") (pintype "passive"))
      (node (ref "EXPWR") (pin "2") (pinfunction "2_2") (pintype "power_in"))
      (node (ref "EXPWR") (pin "2A") (pinfunction "2A_2A") (pintype "power_in"))
      (node (ref "EXPWR") (pin "2B") (pinfunction "2B_2B") (pintype "power_in"))
      (node (ref "EXPWR") (pin "3") (pinfunction "3_3") (pintype "power_in"))
      (node (ref "EXPWR") (pin "3A") (pinfunction "3A_3A") (pintype "power_in"))
      (node (ref "EXPWR") (pin "3B") (pinfunction "3B_3B") (pintype "power_in"))
    )
    (net (code "19") (name "/IRQ_S") (class "Default")
      (node (ref "U1") (pin "42") (pinfunction "PB2_(AIN0/INT2)_42") (pintype "bidirectional"))
      (node (ref "nrf") (pin "1") (pinfunction "1_1") (pintype "passive"))
    )
    (net (code "20") (name "/LCD_POW") (class "Default")
      (node (ref "R581") (pin "1") (pinfunction "1_1") (pintype "passive"))
      (node (ref "U1") (pin "40") (pinfunction "PB0_(XCK/T0)_40") (pintype "bidirectional"))
    )
    (net (code "21") (name "/LD_1") (class "Default")
      (node (ref "R50") (pin "1") (pinfunction "1_1") (pintype "passive"))
      (node (ref "U10") (pin "11") (pinfunction "PD2_(INT0)_11") (pintype "bidirectional"))
    )
    (net (code "22") (name "/LD_2") (class "Default")
      (node (ref "R51") (pin "1") (pinfunction "1_1") (pintype "passive"))
      (node (ref "U10") (pin "14") (pinfunction "PD5_(OC1A)_14") (pintype "bidirectional"))
    )
    (net (code "23") (name "/LD_3") (class "Default")
      (node (ref "R513") (pin "1") (pinfunction "1_1") (pintype "passive"))
      (node (ref "U1") (pin "21") (pinfunction "PC2_(TCK)_21") (pintype "bidirectional"))
    )
    (net (code "24") (name "/LD_4") (class "Default")
      (node (ref "R512") (pin "1") (pinfunction "1_1") (pintype "passive"))
      (node (ref "U1") (pin "22") (pinfunction "PC3_(TMS)_22") (pintype "bidirectional"))
    )
    (net (code "25") (name "/LD_5") (class "Default")
      (node (ref "R511") (pin "1") (pinfunction "1_1") (pintype "passive"))
      (node (ref "U1") (pin "23") (pinfunction "PC4_(TDO)_23") (pintype "bidirectional"))
    )
    (net (code "26") (name "/LD_6") (class "Default")
      (node (ref "R510") (pin "1") (pinfunction "1_1") (pintype "passive"))
      (node (ref "U1") (pin "24") (pinfunction "PC5_(TDI)_24") (pintype "bidirectional"))
    )
    (net (code "27") (name "/LD_7") (class "Default")
      (node (ref "R514") (pin "1") (pinfunction "1_1") (pintype "passive"))
    )
    (net (code "28") (name "/LP") (class "Default")
      (node (ref "LCD") (pin "2") (pinfunction "2_2") (pintype "passive"))
      (node (ref "Q2") (pin "5") (pinfunction "D2_5") (pintype "passive"))
      (node (ref "Q2") (pin "6") (pinfunction "D2_6") (pintype "passive"))
    )
    (net (code "29") (name "/MISO1") (class "Default")
      (node (ref "P1") (pin "2") (pinfunction "2_2") (pintype "passive"))
      (node (ref "U1") (pin "2") (pinfunction "PB6_(MISO)_2") (pintype "bidirectional"))
      (node (ref "nrf") (pin "2") (pinfunction "2_2") (pintype "passive"))
    )
    (net (code "30") (name "/MISO2") (class "Default")
      (node (ref "P2") (pin "2") (pinfunction "2_2") (pintype "passive"))
      (node (ref "U2") (pin "8") (pinfunction "PA5_(ADC5/DO/MISO/OC1B/PCINT5)_8") (pintype "bidirectional"))
    )
    (net (code "31") (name "/MISO3") (class "Default")
      (node (ref "P3") (pin "2") (pinfunction "2_2") (pintype "passive"))
      (node (ref "U3") (pin "8") (pinfunction "PA5_(ADC5/DO/MISO/OC1B/PCINT5)_8") (pintype "bidirectional"))
    )
    (net (code "32") (name "/MISO4") (class "Default")
      (node (ref "P4") (pin "2") (pinfunction "2_2") (pintype "passive"))
      (node (ref "U4") (pin "8") (pinfunction "PA5_(ADC5/DO/MISO/OC1B/PCINT5)_8") (pintype "bidirectional"))
    )
    (net (code "33") (name "/MISO5") (class "Default")
      (node (ref "P5") (pin "2") (pinfunction "2_2") (pintype "passive"))
      (node (ref "U5") (pin "8") (pinfunction "PA5_(ADC5/DO/MISO/OC1B/PCINT5)_8") (pintype "bidirectional"))
    )
    (net (code "34") (name "/MISO6") (class "Default")
      (node (ref "P6") (pin "2") (pinfunction "2_2") (pintype "passive"))
      (node (ref "U6") (pin "8") (pinfunction "PA5_(ADC5/DO/MISO/OC1B/PCINT5)_8") (pintype "bidirectional"))
    )
    (net (code "35") (name "/MISO7") (class "Default")
      (node (ref "MICRO_SD") (pin "7") (pinfunction "D0-MISO_7") (pintype "bidirectional"))
      (node (ref "P49") (pin "2") (pinfunction "2_2") (pintype "passive"))
      (node (ref "U10") (pin "2") (pinfunction "PB6_(MISO)_2") (pintype "bidirectional"))
    )
    (net (code "36") (name "/MOSI1") (class "Default")
      (node (ref "P1") (pin "1") (pinfunction "1_1") (pintype "passive"))
      (node (ref "U1") (pin "1") (pinfunction "PB5_(MOSI)_1") (pintype "bidirectional"))
      (node (ref "nrf") (pin "3") (pinfunction "3_3") (pintype "passive"))
    )
    (net (code "37") (name "/MOSI2") (class "Default")
      (node (ref "P2") (pin "1") (pinfunction "1_1") (pintype "passive"))
      (node (ref "U2") (pin "7") (pinfunction "PA6_(PCINT6/OC1A/SDA/MOSI/DI/ADC6)_7") (pintype "bidirectional"))
    )
    (net (code "38") (name "/MOSI3") (class "Default")
      (node (ref "P3") (pin "1") (pinfunction "1_1") (pintype "passive"))
      (node (ref "U3") (pin "7") (pinfunction "PA6_(PCINT6/OC1A/SDA/MOSI/DI/ADC6)_7") (pintype "bidirectional"))
    )
    (net (code "39") (name "/MOSI4") (class "Default")
      (node (ref "P4") (pin "1") (pinfunction "1_1") (pintype "passive"))
      (node (ref "U4") (pin "7") (pinfunction "PA6_(PCINT6/OC1A/SDA/MOSI/DI/ADC6)_7") (pintype "bidirectional"))
    )
    (net (code "40") (name "/MOSI5") (class "Default")
      (node (ref "P5") (pin "1") (pinfunction "1_1") (pintype "passive"))
      (node (ref "U5") (pin "7") (pinfunction "PA6_(PCINT6/OC1A/SDA/MOSI/DI/ADC6)_7") (pintype "bidirectional"))
    )
    (net (code "41") (name "/MOSI6") (class "Default")
      (node (ref "P6") (pin "1") (pinfunction "1_1") (pintype "passive"))
      (node (ref "U6") (pin "7") (pinfunction "PA6_(PCINT6/OC1A/SDA/MOSI/DI/ADC6)_7") (pintype "bidirectional"))
    )
    (net (code "42") (name "/MOSI7") (class "Default")
      (node (ref "MICRO_SD") (pin "3") (pinfunction "CMD-MOSI_3") (pintype "bidirectional"))
      (node (ref "P49") (pin "1") (pinfunction "1_1") (pintype "passive"))
      (node (ref "U10") (pin "1") (pinfunction "PB5_(MOSI)_1") (pintype "bidirectional"))
    )
    (net (code "43") (name "/RS") (class "Default")
      (node (ref "LCD") (pin "4") (pinfunction "4_4") (pintype "passive"))
      (node (ref "U1") (pin "37") (pinfunction "PA0_(ADC0)_37") (pintype "bidirectional"))
    )
    (net (code "44") (name "/RST1") (class "Default")
      (node (ref "P1") (pin "4") (pinfunction "4_4") (pintype "passive"))
      (node (ref "R14") (pin "2") (pinfunction "2_2") (pintype "passive"))
      (node (ref "S1") (pin "2") (pinfunction "2_2") (pintype "passive"))
      (node (ref "U1") (pin "4") (pinfunction "~{RESET}_4") (pintype "input"))
    )
    (net (code "45") (name "/RST2") (class "Default")
      (node (ref "P2") (pin "4") (pinfunction "4_4") (pintype "passive"))
      (node (ref "R13") (pin "1") (pinfunction "1_1") (pintype "passive"))
      (node (ref "S2") (pin "1") (pinfunction "1_1") (pintype "passive"))
      (node (ref "U2") (pin "4") (pinfunction "PB3_(PCINT11/~{RESET}/dW)_4") (pintype "bidirectional"))
    )
    (net (code "46") (name "/RST3") (class "Default")
      (node (ref "P3") (pin "4") (pinfunction "4_4") (pintype "passive"))
      (node (ref "R12") (pin "1") (pinfunction "1_1") (pintype "passive"))
      (node (ref "S3") (pin "1") (pinfunction "1_1") (pintype "passive"))
      (node (ref "U3") (pin "4") (pinfunction "PB3_(PCINT11/~{RESET}/dW)_4") (pintype "bidirectional"))
    )
    (net (code "47") (name "/RST4") (class "Default")
      (node (ref "P4") (pin "4") (pinfunction "4_4") (pintype "passive"))
      (node (ref "R11") (pin "1") (pinfunction "1_1") (pintype "passive"))
      (node (ref "S4") (pin "1") (pinfunction "1_1") (pintype "passive"))
      (node (ref "U4") (pin "4") (pinfunction "PB3_(PCINT11/~{RESET}/dW)_4") (pintype "bidirectional"))
    )
    (net (code "48") (name "/RST5") (class "Default")
      (node (ref "P5") (pin "4") (pinfunction "4_4") (pintype "passive"))
      (node (ref "R10") (pin "1") (pinfunction "1_1") (pintype "passive"))
      (node (ref "S5") (pin "1") (pinfunction "1_1") (pintype "passive"))
      (node (ref "U5") (pin "4") (pinfunction "PB3_(PCINT11/~{RESET}/dW)_4") (pintype "bidirectional"))
    )
    (net (code "49") (name "/RST6") (class "Default")
      (node (ref "P6") (pin "4") (pinfunction "4_4") (pintype "passive"))
      (node (ref "R9") (pin "1") (pinfunction "1_1") (pintype "passive"))
      (node (ref "S6") (pin "2") (pinfunction "2_2") (pintype "passive"))
      (node (ref "U6") (pin "4") (pinfunction "PB3_(PCINT11/~{RESET}/dW)_4") (pintype "bidirectional"))
    )
    (net (code "50") (name "/RST7") (class "Default")
      (node (ref "P49") (pin "4") (pinfunction "4_4") (pintype "passive"))
      (node (ref "R8") (pin "2") (pinfunction "2_2") (pintype "passive"))
      (node (ref "S7") (pin "1") (pinfunction "1_1") (pintype "passive"))
      (node (ref "U10") (pin "4") (pinfunction "~{RESET}_4") (pintype "input"))
    )
    (net (code "51") (name "/RW") (class "Default")
      (node (ref "LCD") (pin "5") (pinfunction "5_5") (pintype "passive"))
      (node (ref "U1") (pin "36") (pinfunction "PA1_(ADC1)_36") (pintype "bidirectional"))
    )
    (net (code "52") (name "/RX") (class "Default")
      (node (ref "D5") (pin "2") (pinfunction "K_2") (pintype "passive"))
      (node (ref "R6") (pin "1") (pinfunction "1_1") (pintype "passive"))
      (node (ref "U1") (pin "10") (pinfunction "PD1_(TXD)_10") (pintype "bidirectional"))
      (node (ref "U2") (pin "5") (pinfunction "PB2_(PCINT10/INT0/OC0A/CKOUT)_5") (pintype "bidirectional"))
      (node (ref "U3") (pin "5") (pinfunction "PB2_(PCINT10/INT0/OC0A/CKOUT)_5") (pintype "bidirectional"))
      (node (ref "U4") (pin "5") (pinfunction "PB2_(PCINT10/INT0/OC0A/CKOUT)_5") (pintype "bidirectional"))
      (node (ref "U5") (pin "5") (pinfunction "PB2_(PCINT10/INT0/OC0A/CKOUT)_5") (pintype "bidirectional"))
      (node (ref "U6") (pin "5") (pinfunction "PB2_(PCINT10/INT0/OC0A/CKOUT)_5") (pintype "bidirectional"))
    )
    (net (code "53") (name "/RX1") (class "Default")
      (node (ref "R6") (pin "2") (pinfunction "2_2") (pintype "passive"))
      (node (ref "U10") (pin "9") (pinfunction "PD0_(RXD)_9") (pintype "bidirectional"))
      (node (ref "W5") (pin "2") (pinfunction "C2_2") (pintype "passive"))
    )
    (net (code "54") (name "/SCK1") (class "Default")
      (node (ref "P1") (pin "3") (pinfunction "3_3") (pintype "passive"))
      (node (ref "U1") (pin "3") (pinfunction "PB7_(SCK)_3") (pintype "bidirectional"))
      (node (ref "nrf") (pin "4") (pinfunction "4_4") (pintype "passive"))
    )
    (net (code "55") (name "/SCK2") (class "Default")
      (node (ref "P2") (pin "3") (pinfunction "3_3") (pintype "passive"))
      (node (ref "U2") (pin "9") (pinfunction "PA4_(ADC4/USCK/SCL/T1/PCINT4)_9") (pintype "bidirectional"))
    )
    (net (code "56") (name "/SCK3") (class "Default")
      (node (ref "P3") (pin "3") (pinfunction "3_3") (pintype "passive"))
      (node (ref "U3") (pin "9") (pinfunction "PA4_(ADC4/USCK/SCL/T1/PCINT4)_9") (pintype "bidirectional"))
    )
    (net (code "57") (name "/SCK4") (class "Default")
      (node (ref "P4") (pin "3") (pinfunction "3_3") (pintype "passive"))
      (node (ref "U4") (pin "9") (pinfunction "PA4_(ADC4/USCK/SCL/T1/PCINT4)_9") (pintype "bidirectional"))
    )
    (net (code "58") (name "/SCK5") (class "Default")
      (node (ref "P5") (pin "3") (pinfunction "3_3") (pintype "passive"))
      (node (ref "U5") (pin "9") (pinfunction "PA4_(ADC4/USCK/SCL/T1/PCINT4)_9") (pintype "bidirectional"))
    )
    (net (code "59") (name "/SCK6") (class "Default")
      (node (ref "P6") (pin "3") (pinfunction "3_3") (pintype "passive"))
      (node (ref "U6") (pin "9") (pinfunction "PA4_(ADC4/USCK/SCL/T1/PCINT4)_9") (pintype "bidirectional"))
    )
    (net (code "60") (name "/SCK7") (class "Default")
      (node (ref "MICRO_SD") (pin "5") (pinfunction "CLK_5") (pintype "input"))
      (node (ref "P49") (pin "3") (pinfunction "3_3") (pintype "passive"))
      (node (ref "U10") (pin "3") (pinfunction "PB7_(SCK)_3") (pintype "bidirectional"))
    )
    (net (code "61") (name "/SCL") (class "Default")
      (node (ref "U1") (pin "19") (pinfunction "PC0_(SCL)_19") (pintype "bidirectional"))
      (node (ref "U11") (pin "6") (pinfunction "MISO/PB1_6") (pintype "bidirectional"))
    )
    (net (code "62") (name "/SDA") (class "Default")
      (node (ref "U1") (pin "20") (pinfunction "PC1_(SDA)_20") (pintype "bidirectional"))
      (node (ref "U11") (pin "5") (pinfunction "MOSI/PB0_5") (pintype "bidirectional"))
    )
    (net (code "63") (name "/TX") (class "Default")
      (node (ref "U1") (pin "9") (pinfunction "PD0_(RXD)_9") (pintype "bidirectional"))
      (node (ref "U2") (pin "12") (pinfunction "PA1_(ADC1/AIN0/PCINT1)_12") (pintype "bidirectional"))
      (node (ref "U3") (pin "12") (pinfunction "PA1_(ADC1/AIN0/PCINT1)_12") (pintype "bidirectional"))
      (node (ref "U4") (pin "12") (pinfunction "PA1_(ADC1/AIN0/PCINT1)_12") (pintype "bidirectional"))
      (node (ref "U5") (pin "12") (pinfunction "PA1_(ADC1/AIN0/PCINT1)_12") (pintype "bidirectional"))
      (node (ref "U6") (pin "12") (pinfunction "PA1_(ADC1/AIN0/PCINT1)_12") (pintype "bidirectional"))
    )
    (net (code "64") (name "/VBAT") (class "Default")
      (node (ref "U11") (pin "3") (pinfunction "OC1B/PB4_3") (pintype "bidirectional"))
      (node (ref "battry") (pin "1") (pinfunction "1_1") (pintype "passive"))
    )
    (net (code "65") (name "/VDD") (class "Default")
      (node (ref "MICRO_SD") (pin "4") (pinfunction "VDD_4") (pintype "power_in"))
      (node (ref "Q1") (pin "5") (pinfunction "D2_5") (pintype "passive"))
      (node (ref "Q1") (pin "6") (pinfunction "D2_6") (pintype "passive"))
    )
    (net (code "66") (name "/card_ins") (class "Default")
      (node (ref "MICRO_SD") (pin "9") (pinfunction "SW2_9") (pintype "passive"))
      (node (ref "R48") (pin "2") (pinfunction "2_2") (pintype "passive"))
      (node (ref "U10") (pin "42") (pinfunction "PB2_(AIN0/INT2)_42") (pintype "bidirectional"))
    )
    (net (code "67") (name "/nCS") (class "Default")
      (node (ref "MICRO_SD") (pin "2") (pinfunction "D3-CD/NSS_2") (pintype "bidirectional"))
      (node (ref "U10") (pin "44") (pinfunction "PB4_(~{SS})_44") (pintype "bidirectional"))
    )
    (net (code "68") (name "/sd_power") (class "Default")
      (node (ref "R58") (pin "1") (pinfunction "1_1") (pintype "passive"))
      (node (ref "U10") (pin "13") (pinfunction "PD4_(OC1B)_13") (pintype "bidirectional"))
    )
    (net (code "69") (name "3.3") (class "Default")
      (node (ref "C26") (pin "1") (pinfunction "1_1") (pintype "passive"))
      (node (ref "C4") (pin "1") (pinfunction "1_1") (pintype "passive"))
      (node (ref "C5") (pin "1") (pinfunction "1_1") (pintype "passive"))
      (node (ref "C9") (pin "1") (pinfunction "1_1") (pintype "passive"))
      (node (ref "D3") (pin "1") (pinfunction "A_1") (pintype "passive"))
      (node (ref "Q1") (pin "3") (pinfunction "S2_3") (pintype "passive"))
      (node (ref "R48") (pin "1") (pinfunction "1_1") (pintype "passive"))
      (node (ref "R8") (pin "1") (pinfunction "1_1") (pintype "passive"))
      (node (ref "U10") (pin "17") (pinfunction "VCC_17") (pintype "power_in"))
      (node (ref "U10") (pin "27") (pinfunction "AVCC_27") (pintype "power_in"))
      (node (ref "U10") (pin "38") (pinfunction "VCC_38") (pintype "power_in"))
      (node (ref "U10") (pin "5") (pinfunction "VCC_5") (pintype "power_in"))
      (node (ref "U9") (pin "3") (pinfunction "OUT_3") (pintype "power_in"))
      (node (ref "nrf") (pin "7") (pinfunction "7_7") (pintype "passive"))
    )
    (net (code "70") (name "5") (class "Default")
      (node (ref "C10") (pin "1") (pinfunction "1_1") (pintype "passive"))
      (node (ref "C27") (pin "1") (pinfunction "1_1") (pintype "passive"))
      (node (ref "C28") (pin "1") (pinfunction "1_1") (pintype "passive"))
      (node (ref "C29") (pin "1") (pinfunction "1_1") (pintype "passive"))
      (node (ref "C3") (pin "1") (pinfunction "1_1") (pintype "passive"))
      (node (ref "C30") (pin "1") (pinfunction "1_1") (pintype "passive"))
      (node (ref "C31") (pin "1") (pinfunction "1_1") (pintype "passive"))
      (node (ref "C32") (pin "1") (pinfunction "1_1") (pintype "passive"))
      (node (ref "D2") (pin "1") (pinfunction "A_1") (pintype "passive"))
      (node (ref "LCD") (pin "15") (pinfunction "15_15") (pintype "passive"))
      (node (ref "P10") (pin "1") (pinfunction "1_1") (pintype "passive"))
      (node (ref "P11") (pin "1") (pinfunction "1_1") (pintype "passive"))
      (node (ref "P12") (pin "1") (pinfunction "1_1") (pintype "passive"))
      (node (ref "P13") (pin "1") (pinfunction "1_1") (pintype "passive"))
      (node (ref "P14") (pin "1") (pinfunction "1_1") (pintype "passive"))
      (node (ref "P15") (pin "1") (pinfunction "1_1") (pintype "passive"))
      (node (ref "P16") (pin "1") (pinfunction "1_1") (pintype "passive"))
      (node (ref "P17") (pin "1") (pinfunction "1_1") (pintype "passive"))
      (node (ref "P18") (pin "1") (pinfunction "1_1") (pintype "passive"))
      (node (ref "P19") (pin "1") (pinfunction "1_1") (pintype "passive"))
      (node (ref "P20") (pin "1") (pinfunction "1_1") (pintype "passive"))
      (node (ref "P21") (pin "1") (pinfunction "1_1") (pintype "passive"))
      (node (ref "P22") (pin "1") (pinfunction "1_1") (pintype "passive"))
      (node (ref "P23") (pin "1") (pinfunction "1_1") (pintype "passive"))
      (node (ref "P24") (pin "1") (pinfunction "1_1") (pintype "passive"))
      (node (ref "P25") (pin "1") (pinfunction "1_1") (pintype "passive"))
      (node (ref "P26") (pin "1") (pinfunction "1_1") (pintype "passive"))
      (node (ref "P27") (pin "1") (pinfunction "1_1") (pintype "passive"))
      (node (ref "P28") (pin "1") (pinfunction "1_1") (pintype "passive"))
      (node (ref "P29") (pin "1") (pinfunction "1_1") (pintype "passive"))
      (node (ref "P30") (pin "1") (pinfunction "1_1") (pintype "passive"))
      (node (ref "P31") (pin "1") (pinfunction "1_1") (pintype "passive"))
      (node (ref "P32") (pin "1") (pinfunction "1_1") (pintype "passive"))
      (node (ref "P33") (pin "1") (pinfunction "1_1") (pintype "passive"))
      (node (ref "P34") (pin "1") (pinfunction "1_1") (pintype "passive"))
      (node (ref "P35") (pin "1") (pinfunction "1_1") (pintype "passive"))
      (node (ref "P36") (pin "1") (pinfunction "1_1") (pintype "passive"))
      (node (ref "P37") (pin "1") (pinfunction "1_1") (pintype "passive"))
      (node (ref "P38") (pin "1") (pinfunction "1_1") (pintype "passive"))
      (node (ref "P39") (pin "1") (pinfunction "1_1") (pintype "passive"))
      (node (ref "P40") (pin "1") (pinfunction "1_1") (pintype "passive"))
      (node (ref "P41") (pin "1") (pinfunction "1_1") (pintype "passive"))
      (node (ref "P42") (pin "1") (pinfunction "1_1") (pintype "passive"))
      (node (ref "P43") (pin "1") (pinfunction "1_1") (pintype "passive"))
      (node (ref "P44") (pin "1") (pinfunction "1_1") (pintype "passive"))
      (node (ref "P45") (pin "1") (pinfunction "1_1") (pintype "passive"))
      (node (ref "P46") (pin "1") (pinfunction "1_1") (pintype "passive"))
      (node (ref "P7") (pin "1") (pinfunction "1_1") (pintype "passive"))
      (node (ref "P8") (pin "1") (pinfunction "1_1") (pintype "passive"))
      (node (ref "P9") (pin "1") (pinfunction "1_1") (pintype "passive"))
      (node (ref "Q2") (pin "3") (pinfunction "S2_3") (pintype "passive"))
      (node (ref "R1") (pin "2") (pinfunction "2_2") (pintype "passive"))
      (node (ref "R10") (pin "2") (pinfunction "2_2") (pintype "passive"))
      (node (ref "R11") (pin "2") (pinfunction "2_2") (pintype "passive"))
      (node (ref "R12") (pin "2") (pinfunction "2_2") (pintype "passive"))
      (node (ref "R13") (pin "2") (pinfunction "2_2") (pintype "passive"))
      (node (ref "R14") (pin "1") (pinfunction "1_1") (pintype "passive"))
      (node (ref "R2") (pin "2") (pinfunction "2_2") (pintype "passive"))
      (node (ref "R3") (pin "2") (pinfunction "2_2") (pintype "passive"))
      (node (ref "R4") (pin "2") (pinfunction "2_2") (pintype "passive"))
      (node (ref "R5") (pin "2") (pinfunction "2_2") (pintype "passive"))
      (node (ref "R9") (pin "2") (pinfunction "2_2") (pintype "passive"))
      (node (ref "U1") (pin "17") (pinfunction "VCC_17") (pintype "power_in"))
      (node (ref "U1") (pin "27") (pinfunction "AVCC_27") (pintype "power_in"))
      (node (ref "U1") (pin "38") (pinfunction "VCC_38") (pintype "power_in"))
      (node (ref "U1") (pin "5") (pinfunction "VCC_5") (pintype "power_in"))
      (node (ref "U11") (pin "8") (pinfunction "VCC_8") (pintype "power_in"))
      (node (ref "U2") (pin "1") (pinfunction "VCC_1") (pintype "power_in"))
      (node (ref "U3") (pin "1") (pinfunction "VCC_1") (pintype "power_in"))
      (node (ref "U4") (pin "1") (pinfunction "VCC_1") (pintype "power_in"))
      (node (ref "U5") (pin "1") (pinfunction "VCC_1") (pintype "power_in"))
      (node (ref "U6") (pin "1") (pinfunction "VCC_1") (pintype "power_in"))
      (node (ref "U8") (pin "2") (pinfunction "OUT_2") (pintype "power_in"))
      (node (ref "U9") (pin "1") (pinfunction "IN_1") (pintype "power_in"))
      (node (ref "VR1") (pin "3") (pinfunction "TAP_3") (pintype "passive"))
    )
    (net (code "71") (name "9") (class "Default")
      (node (ref "C11") (pin "1") (pinfunction "1_1") (pintype "passive"))
      (node (ref "C2") (pin "1") (pinfunction "1_1") (pintype "passive"))
      (node (ref "U7") (pin "2") (pinfunction "OUT_2") (pintype "power_in"))
      (node (ref "U8") (pin "1") (pinfunction "IN_1") (pintype "power_in"))
    )
    (net (code "72") (name "12") (class "Default")
      (node (ref "C1") (pin "1") (pinfunction "1_1") (pintype "passive"))
      (node (ref "D1") (pin "1") (pinfunction "A_1") (pintype "passive"))
      (node (ref "P47") (pin "2") (pinfunction "2_2") (pintype "passive"))
      (node (ref "U7") (pin "1") (pinfunction "IN_1") (pintype "power_in"))
    )
    (net (code "73") (name "GND") (class "Default")
      (node (ref "C1") (pin "2") (pinfunction "2_2") (pintype "passive"))
      (node (ref "C10") (pin "2") (pinfunction "2_2") (pintype "passive"))
      (node (ref "C11") (pin "2") (pinfunction "2_2") (pintype "passive"))
      (node (ref "C12") (pin "2") (pinfunction "2_2") (pintype "passive"))
      (node (ref "C13") (pin "2") (pinfunction "2_2") (pintype "passive"))
      (node (ref "C14") (pin "2") (pinfunction "2_2") (pintype "passive"))
      (node (ref "C15") (pin "2") (pinfunction "2_2") (pintype "passive"))
      (node (ref "C16") (pin "2") (pinfunction "2_2") (pintype "passive"))
      (node (ref "C17") (pin "2") (pinfunction "2_2") (pintype "passive"))
      (node (ref "C18") (pin "2") (pinfunction "2_2") (pintype "passive"))
      (node (ref "C19") (pin "2") (pinfunction "2_2") (pintype "passive"))
      (node (ref "C2") (pin "2") (pinfunction "2_2") (pintype "passive"))
      (node (ref "C20") (pin "2") (pinfunction "2_2") (pintype "passive"))
      (node (ref "C21") (pin "2") (pinfunction "2_2") (pintype "passive"))
      (node (ref "C22") (pin "2") (pinfunction "2_2") (pintype "passive"))
      (node (ref "C23") (pin "2") (pinfunction "2_2") (pintype "passive"))
      (node (ref "C24") (pin "2") (pinfunction "2_2") (pintype "passive"))
      (node (ref "C25") (pin "2") (pinfunction "2_2") (pintype "passive"))
      (node (ref "C26") (pin "2") (pinfunction "2_2") (pintype "passive"))
      (node (ref "C27") (pin "2") (pinfunction "2_2") (pintype "passive"))
      (node (ref "C28") (pin "2") (pinfunction "2_2") (pintype "passive"))
      (node (ref "C29") (pin "2") (pinfunction "2_2") (pintype "passive"))
      (node (ref "C3") (pin "2") (pinfunction "2_2") (pintype "passive"))
      (node (ref "C30") (pin "2") (pinfunction "2_2") (pintype "passive"))
      (node (ref "C31") (pin "2") (pinfunction "2_2") (pintype "passive"))
      (node (ref "C32") (pin "2") (pinfunction "2_2") (pintype "passive"))
      (node (ref "C4") (pin "2") (pinfunction "2_2") (pintype "passive"))
      (node (ref "C5") (pin "2") (pinfunction "2_2") (pintype "passive"))
      (node (ref "C9") (pin "2") (pinfunction "2_2") (pintype "passive"))
      (node (ref "DR1") (pin "1") (pinfunction "A_1") (pintype "passive"))
      (node (ref "DR2") (pin "1") (pinfunction "A_1") (pintype "passive"))
      (node (ref "LCD") (pin "1") (pinfunction "1_1") (pintype "passive"))
      (node (ref "LEDS") (pin "8") (pinfunction "8_8") (pintype "passive"))
      (node (ref "MICRO_SD") (pin "6") (pinfunction "VSS_6") (pintype "power_in"))
      (node (ref "MICRO_SD") (pin "sh1") (pinfunction "sh1_sh1") (pintype "passive"))
      (node (ref "MICRO_SD") (pin "sh2") (pinfunction "sh2_sh2") (pintype "passive"))
      (node (ref "MICRO_SD") (pin "sh3") (pinfunction "sh3_sh3") (pintype "passive"))
      (node (ref "MICRO_SD") (pin "sh4") (pinfunction "sh4_sh4") (pintype "passive"))
      (node (ref "P10") (pin "4") (pinfunction "4_4") (pintype "passive"))
      (node (ref "P11") (pin "4") (pinfunction "4_4") (pintype "passive"))
      (node (ref "P12") (pin "4") (pinfunction "4_4") (pintype "passive"))
      (node (ref "P13") (pin "4") (pinfunction "4_4") (pintype "passive"))
      (node (ref "P14") (pin "4") (pinfunction "4_4") (pintype "passive"))
      (node (ref "P15") (pin "4") (pinfunction "4_4") (pintype "passive"))
      (node (ref "P16") (pin "4") (pinfunction "4_4") (pintype "passive"))
      (node (ref "P17") (pin "4") (pinfunction "4_4") (pintype "passive"))
      (node (ref "P18") (pin "4") (pinfunction "4_4") (pintype "passive"))
      (node (ref "P19") (pin "4") (pinfunction "4_4") (pintype "passive"))
      (node (ref "P20") (pin "4") (pinfunction "4_4") (pintype "passive"))
      (node (ref "P21") (pin "4") (pinfunction "4_4") (pintype "passive"))
      (node (ref "P22") (pin "4") (pinfunction "4_4") (pintype "passive"))
      (node (ref "P23") (pin "4") (pinfunction "4_4") (pintype "passive"))
      (node (ref "P24") (pin "4") (pinfunction "4_4") (pintype "passive"))
      (node (ref "P25") (pin "4") (pinfunction "4_4") (pintype "passive"))
      (node (ref "P26") (pin "4") (pinfunction "4_4") (pintype "passive"))
      (node (ref "P27") (pin "4") (pinfunction "4_4") (pintype "passive"))
      (node (ref "P28") (pin "4") (pinfunction "4_4") (pintype "passive"))
      (node (ref "P29") (pin "4") (pinfunction "4_4") (pintype "passive"))
      (node (ref "P30") (pin "4") (pinfunction "4_4") (pintype "passive"))
      (node (ref "P31") (pin "4") (pinfunction "4_4") (pintype "passive"))
      (node (ref "P32") (pin "4") (pinfunction "4_4") (pintype "passive"))
      (node (ref "P33") (pin "4") (pinfunction "4_4") (pintype "passive"))
      (node (ref "P34") (pin "4") (pinfunction "4_4") (pintype "passive"))
      (node (ref "P35") (pin "4") (pinfunction "4_4") (pintype "passive"))
      (node (ref "P36") (pin "4") (pinfunction "4_4") (pintype "passive"))
      (node (ref "P37") (pin "4") (pinfunction "4_4") (pintype "passive"))
      (node (ref "P38") (pin "4") (pinfunction "4_4") (pintype "passive"))
      (node (ref "P39") (pin "4") (pinfunction "4_4") (pintype "passive"))
      (node (ref "P40") (pin "4") (pinfunction "4_4") (pintype "passive"))
      (node (ref "P41") (pin "4") (pinfunction "4_4") (pintype "passive"))
      (node (ref "P42") (pin "4") (pinfunction "4_4") (pintype "passive"))
      (node (ref "P43") (pin "4") (pinfunction "4_4") (pintype "passive"))
      (node (ref "P44") (pin "4") (pinfunction "4_4") (pintype "passive"))
      (node (ref "P45") (pin "4") (pinfunction "4_4") (pintype "passive"))
      (node (ref "P46") (pin "4") (pinfunction "4_4") (pintype "passive"))
      (node (ref "P7") (pin "4") (pinfunction "4_4") (pintype "passive"))
      (node (ref "P8") (pin "4") (pinfunction "4_4") (pintype "passive"))
      (node (ref "P9") (pin "4") (pinfunction "4_4") (pintype "passive"))
      (node (ref "Q2") (pin "1") (pinfunction "S1_1") (pintype "passive"))
      (node (ref "R15") (pin "1") (pinfunction "1_1") (pintype "passive"))
      (node (ref "R16") (pin "1") (pinfunction "1_1") (pintype "passive"))
      (node (ref "R17") (pin "1") (pinfunction "1_1") (pintype "passive"))
      (node (ref "R18") (pin "1") (pinfunction "1_1") (pintype "passive"))
      (node (ref "R7") (pin "2") (pinfunction "2_2") (pintype "passive"))
      (node (ref "S1") (pin "1") (pinfunction "1_1") (pintype "passive"))
      (node (ref "S2") (pin "2") (pinfunction "2_2") (pintype "passive"))
      (node (ref "S3") (pin "2") (pinfunction "2_2") (pintype "passive"))
      (node (ref "S4") (pin "2") (pinfunction "2_2") (pintype "passive"))
      (node (ref "S5") (pin "2") (pinfunction "2_2") (pintype "passive"))
      (node (ref "S6") (pin "1") (pinfunction "1_1") (pintype "passive"))
      (node (ref "S7") (pin "2") (pinfunction "2_2") (pintype "passive"))
      (node (ref "U1") (pin "18") (pinfunction "GND_18") (pintype "power_in"))
      (node (ref "U1") (pin "28") (pinfunction "GND_28") (pintype "power_in"))
      (node (ref "U1") (pin "39") (pinfunction "GND_39") (pintype "power_in"))
      (node (ref "U1") (pin "6") (pinfunction "GND_6") (pintype "power_in"))
      (node (ref "U10") (pin "18") (pinfunction "GND_18") (pintype "power_in"))
      (node (ref "U10") (pin "28") (pinfunction "GND_28") (pintype "power_in"))
      (node (ref "U10") (pin "39") (pinfunction "GND_39") (pintype "power_in"))
      (node (ref "U10") (pin "6") (pinfunction "GND_6") (pintype "power_in"))
      (node (ref "U11") (pin "4") (pinfunction "GND_4") (pintype "power_in"))
      (node (ref "U2") (pin "14") (pinfunction "GND_14") (pintype "power_in"))
      (node (ref "U3") (pin "14") (pinfunction "GND_14") (pintype "power_in"))
      (node (ref "U4") (pin "14") (pinfunction "GND_14") (pintype "power_in"))
      (node (ref "U5") (pin "14") (pinfunction "GND_14") (pintype "power_in"))
      (node (ref "U6") (pin "14") (pinfunction "GND_14") (pintype "power_in"))
      (node (ref "U7") (pin "3") (pinfunction "GND_3") (pintype "power_in"))
      (node (ref "U8") (pin "3") (pinfunction "GND_3") (pintype "power_in"))
      (node (ref "U9") (pin "2") (pinfunction "GND_2") (pintype "power_in"))
      (node (ref "VR1") (pin "1") (pinfunction "A_1") (pintype "passive"))
      (node (ref "battry") (pin "2") (pinfunction "2_2") (pintype "passive"))
      (node (ref "nrf") (pin "8") (pinfunction "8_8") (pintype "passive"))
    )
    (net (code "74") (name "Net-(D1-K)") (class "Default")
      (node (ref "D1") (pin "2") (pinfunction "K_2") (pintype "passive"))
      (node (ref "R15") (pin "2") (pinfunction "2_2") (pintype "passive"))
    )
    (net (code "75") (name "Net-(D2-K)") (class "Default")
      (node (ref "D2") (pin "2") (pinfunction "K_2") (pintype "passive"))
      (node (ref "R16") (pin "2") (pinfunction "2_2") (pintype "passive"))
    )
    (net (code "76") (name "Net-(D3-K)") (class "Default")
      (node (ref "D3") (pin "2") (pinfunction "K_2") (pintype "passive"))
      (node (ref "R17") (pin "2") (pinfunction "2_2") (pintype "passive"))
    )
    (net (code "77") (name "Net-(D4-K)") (class "Default")
      (node (ref "D4") (pin "2") (pinfunction "K_2") (pintype "passive"))
      (node (ref "R18") (pin "2") (pinfunction "2_2") (pintype "passive"))
    )
    (net (code "78") (name "Net-(D5-A)") (class "Default")
      (node (ref "D5") (pin "1") (pinfunction "A_1") (pintype "passive"))
      (node (ref "U10") (pin "10") (pinfunction "PD1_(TXD)_10") (pintype "bidirectional"))
    )
    (net (code "79") (name "Net-(DR3-K)") (class "Default")
      (node (ref "DR3") (pin "2") (pinfunction "K_2") (pintype "passive"))
      (node (ref "DR4") (pin "2") (pinfunction "K_2") (pintype "passive"))
      (node (ref "P47") (pin "1") (pinfunction "1_1") (pintype "passive"))
    )
    (net (code "80") (name "Net-(LEDS-Pad1)") (class "Default")
      (node (ref "LEDS") (pin "1") (pinfunction "1_1") (pintype "passive"))
      (node (ref "R50") (pin "2") (pinfunction "2_2") (pintype "passive"))
    )
    (net (code "81") (name "Net-(LEDS-Pad2)") (class "Default")
      (node (ref "LEDS") (pin "2") (pinfunction "2_2") (pintype "passive"))
      (node (ref "R51") (pin "2") (pinfunction "2_2") (pintype "passive"))
    )
    (net (code "82") (name "Net-(LEDS-Pad3)") (class "Default")
      (node (ref "LEDS") (pin "3") (pinfunction "3_3") (pintype "passive"))
      (node (ref "R510") (pin "2") (pinfunction "2_2") (pintype "passive"))
    )
    (net (code "83") (name "Net-(LEDS-Pad4)") (class "Default")
      (node (ref "LEDS") (pin "4") (pinfunction "4_4") (pintype "passive"))
      (node (ref "R511") (pin "2") (pinfunction "2_2") (pintype "passive"))
    )
    (net (code "84") (name "Net-(LEDS-Pad5)") (class "Default")
      (node (ref "LEDS") (pin "5") (pinfunction "5_5") (pintype "passive"))
      (node (ref "R512") (pin "2") (pinfunction "2_2") (pintype "passive"))
    )
    (net (code "85") (name "Net-(LEDS-Pad6)") (class "Default")
      (node (ref "LEDS") (pin "6") (pinfunction "6_6") (pintype "passive"))
      (node (ref "R513") (pin "2") (pinfunction "2_2") (pintype "passive"))
    )
    (net (code "86") (name "Net-(LEDS-Pad7)") (class "Default")
      (node (ref "LEDS") (pin "7") (pinfunction "7_7") (pintype "passive"))
      (node (ref "R514") (pin "2") (pinfunction "2_2") (pintype "passive"))
    )
    (net (code "87") (name "Net-(Q1-D1-Pad7)") (class "Default")
      (node (ref "Q1") (pin "7") (pinfunction "D1_7") (pintype "passive"))
      (node (ref "Q1") (pin "8") (pinfunction "D1_8") (pintype "passive"))
    )
    (net (code "88") (name "Net-(Q1-G2)") (class "Default")
      (node (ref "Q1") (pin "4") (pinfunction "G2_4") (pintype "passive"))
      (node (ref "R58") (pin "2") (pinfunction "2_2") (pintype "passive"))
    )
    (net (code "89") (name "Net-(Q2-G1)") (class "Default")
      (node (ref "Q2") (pin "2") (pinfunction "G1_2") (pintype "passive"))
      (node (ref "R580") (pin "2") (pinfunction "2_2") (pintype "passive"))
    )
    (net (code "90") (name "Net-(Q2-G2)") (class "Default")
      (node (ref "Q2") (pin "4") (pinfunction "G2_4") (pintype "passive"))
      (node (ref "R581") (pin "2") (pinfunction "2_2") (pintype "passive"))
    )
    (net (code "91") (name "Net-(U1-XTAL1)") (class "Default")
      (node (ref "C13") (pin "1") (pinfunction "1_1") (pintype "passive"))
      (node (ref "U1") (pin "8") (pinfunction "XTAL1_8") (pintype "passive"))
      (node (ref "Y1") (pin "1") (pinfunction "OSC1_1") (pintype "passive"))
    )
    (net (code "92") (name "Net-(U1-XTAL2)") (class "Default")
      (node (ref "C12") (pin "1") (pinfunction "1_1") (pintype "passive"))
      (node (ref "U1") (pin "7") (pinfunction "XTAL2_7") (pintype "passive"))
      (node (ref "Y1") (pin "2") (pinfunction "OSC2_2") (pintype "passive"))
    )
    (net (code "93") (name "Net-(U2-PB0_(PCINT8{slash}XTAL1{slash}CLKI))") (class "Default")
      (node (ref "C14") (pin "1") (pinfunction "1_1") (pintype "passive"))
      (node (ref "U2") (pin "2") (pinfunction "PB0_(PCINT8/XTAL1/CLKI)_2") (pintype "bidirectional"))
      (node (ref "Y2") (pin "2") (pinfunction "OSC2_2") (pintype "passive"))
    )
    (net (code "94") (name "Net-(U2-PB1_(PCINT9{slash}XTAL2))") (class "Default")
      (node (ref "C15") (pin "1") (pinfunction "1_1") (pintype "passive"))
      (node (ref "U2") (pin "3") (pinfunction "PB1_(PCINT9/XTAL2)_3") (pintype "bidirectional"))
      (node (ref "Y2") (pin "1") (pinfunction "OSC1_1") (pintype "passive"))
    )
    (net (code "95") (name "Net-(U3-PB0_(PCINT8{slash}XTAL1{slash}CLKI))") (class "Default")
      (node (ref "C16") (pin "1") (pinfunction "1_1") (pintype "passive"))
      (node (ref "U3") (pin "2") (pinfunction "PB0_(PCINT8/XTAL1/CLKI)_2") (pintype "bidirectional"))
      (node (ref "Y3") (pin "2") (pinfunction "OSC2_2") (pintype "passive"))
    )
    (net (code "96") (name "Net-(U3-PB1_(PCINT9{slash}XTAL2))") (class "Default")
      (node (ref "C17") (pin "1") (pinfunction "1_1") (pintype "passive"))
      (node (ref "U3") (pin "3") (pinfunction "PB1_(PCINT9/XTAL2)_3") (pintype "bidirectional"))
      (node (ref "Y3") (pin "1") (pinfunction "OSC1_1") (pintype "passive"))
    )
    (net (code "97") (name "Net-(U4-PB0_(PCINT8{slash}XTAL1{slash}CLKI))") (class "Default")
      (node (ref "C18") (pin "1") (pinfunction "1_1") (pintype "passive"))
      (node (ref "U4") (pin "2") (pinfunction "PB0_(PCINT8/XTAL1/CLKI)_2") (pintype "bidirectional"))
      (node (ref "Y4") (pin "2") (pinfunction "OSC2_2") (pintype "passive"))
    )
    (net (code "98") (name "Net-(U4-PB1_(PCINT9{slash}XTAL2))") (class "Default")
      (node (ref "C19") (pin "1") (pinfunction "1_1") (pintype "passive"))
      (node (ref "U4") (pin "3") (pinfunction "PB1_(PCINT9/XTAL2)_3") (pintype "bidirectional"))
      (node (ref "Y4") (pin "1") (pinfunction "OSC1_1") (pintype "passive"))
    )
    (net (code "99") (name "Net-(U5-PB0_(PCINT8{slash}XTAL1{slash}CLKI))") (class "Default")
      (node (ref "C20") (pin "1") (pinfunction "1_1") (pintype "passive"))
      (node (ref "U5") (pin "2") (pinfunction "PB0_(PCINT8/XTAL1/CLKI)_2") (pintype "bidirectional"))
      (node (ref "Y5") (pin "2") (pinfunction "OSC2_2") (pintype "passive"))
    )
    (net (code "100") (name "Net-(U5-PB1_(PCINT9{slash}XTAL2))") (class "Default")
      (node (ref "C21") (pin "1") (pinfunction "1_1") (pintype "passive"))
      (node (ref "U5") (pin "3") (pinfunction "PB1_(PCINT9/XTAL2)_3") (pintype "bidirectional"))
      (node (ref "Y5") (pin "1") (pinfunction "OSC1_1") (pintype "passive"))
    )
    (net (code "101") (name "Net-(U6-PB0_(PCINT8{slash}XTAL1{slash}CLKI))") (class "Default")
      (node (ref "C22") (pin "1") (pinfunction "1_1") (pintype "passive"))
      (node (ref "U6") (pin "2") (pinfunction "PB0_(PCINT8/XTAL1/CLKI)_2") (pintype "bidirectional"))
      (node (ref "Y6") (pin "2") (pinfunction "OSC2_2") (pintype "passive"))
    )
    (net (code "102") (name "Net-(U6-PB1_(PCINT9{slash}XTAL2))") (class "Default")
      (node (ref "C23") (pin "1") (pinfunction "1_1") (pintype "passive"))
      (node (ref "U6") (pin "3") (pinfunction "PB1_(PCINT9/XTAL2)_3") (pintype "bidirectional"))
      (node (ref "Y6") (pin "1") (pinfunction "OSC1_1") (pintype "passive"))
    )
    (net (code "103") (name "Net-(U10-XTAL1)") (class "Default")
      (node (ref "C24") (pin "1") (pinfunction "1_1") (pintype "passive"))
      (node (ref "U10") (pin "8") (pinfunction "XTAL1_8") (pintype "passive"))
      (node (ref "Y8") (pin "1") (pinfunction "OSC1_1") (pintype "passive"))
    )
    (net (code "104") (name "Net-(U10-XTAL2)") (class "Default")
      (node (ref "C25") (pin "1") (pinfunction "1_1") (pintype "passive"))
      (node (ref "U10") (pin "7") (pinfunction "XTAL2_7") (pintype "passive"))
      (node (ref "Y8") (pin "2") (pinfunction "OSC2_2") (pintype "passive"))
    )
    (net (code "105") (name "Net-(U11-OC1B{slash}PB3)") (class "Default")
      (node (ref "U11") (pin "2") (pinfunction "OC1B/PB3_2") (pintype "bidirectional"))
      (node (ref "Y7") (pin "2") (pinfunction "OSC2_2") (pintype "passive"))
    )
    (net (code "106") (name "Net-(U11-RESET{slash}PB5)") (class "Default")
      (node (ref "U11") (pin "1") (pinfunction "RESET/PB5_1") (pintype "bidirectional"))
      (node (ref "Y7") (pin "1") (pinfunction "OSC1_1") (pintype "passive"))
    )
    (net (code "107") (name "Net-(VR1-B)") (class "Default")
      (node (ref "LCD") (pin "3") (pinfunction "3_3") (pintype "passive"))
      (node (ref "VR1") (pin "2") (pinfunction "B_2") (pintype "passive"))
    )
    (net (code "108") (name "Net-(W5-C1)") (class "Default")
      (node (ref "R7") (pin "1") (pinfunction "1_1") (pintype "passive"))
      (node (ref "W5") (pin "1") (pinfunction "C1_1") (pintype "passive"))
    )
    (net (code "109") (name "SW1") (class "Default")
      (node (ref "MICRO_SD") (pin "10") (pinfunction "SW1_10") (pintype "passive"))
    )
    (net (code "110") (name "sw2") (class "Default")
      (node (ref "D4") (pin "1") (pinfunction "A_1") (pintype "passive"))
      (node (ref "P47") (pin "3") (pinfunction "3_3") (pintype "passive"))
    )
    (net (code "111") (name "unconnected-(LCD-Pad7)") (class "Default")
      (node (ref "LCD") (pin "7") (pinfunction "7_7") (pintype "passive+no_connect"))
    )
    (net (code "112") (name "unconnected-(LCD-Pad8)") (class "Default")
      (node (ref "LCD") (pin "8") (pinfunction "8_8") (pintype "passive+no_connect"))
    )
    (net (code "113") (name "unconnected-(LCD-Pad9)") (class "Default")
      (node (ref "LCD") (pin "9") (pinfunction "9_9") (pintype "passive+no_connect"))
    )
    (net (code "114") (name "unconnected-(LCD-Pad10)") (class "Default")
      (node (ref "LCD") (pin "10") (pinfunction "10_10") (pintype "passive+no_connect"))
    )
    (net (code "115") (name "unconnected-(Q1-G1-Pad2)") (class "Default")
      (node (ref "Q1") (pin "2") (pinfunction "G1_2") (pintype "passive"))
    )
    (net (code "116") (name "unconnected-(Q1-S1-Pad1)") (class "Default")
      (node (ref "Q1") (pin "1") (pinfunction "S1_1") (pintype "passive"))
    )
    (net (code "117") (name "unconnected-(U1-AREF-Pad29)") (class "Default")
      (node (ref "U1") (pin "29") (pinfunction "AREF_29") (pintype "passive"))
    )
    (net (code "118") (name "unconnected-(U1-PA3_(ADC3)-Pad34)") (class "Default")
      (node (ref "U1") (pin "34") (pinfunction "PA3_(ADC3)_34") (pintype "bidirectional"))
    )
    (net (code "119") (name "unconnected-(U1-PC6_(TOSC1)-Pad25)") (class "Default")
      (node (ref "U1") (pin "25") (pinfunction "PC6_(TOSC1)_25") (pintype "bidirectional"))
    )
    (net (code "120") (name "unconnected-(U1-PC7_(TOSC2)-Pad26)") (class "Default")
      (node (ref "U1") (pin "26") (pinfunction "PC7_(TOSC2)_26") (pintype "bidirectional"))
    )
    (net (code "121") (name "unconnected-(U1-PD2_(INT0)-Pad11)") (class "Default")
      (node (ref "U1") (pin "11") (pinfunction "PD2_(INT0)_11") (pintype "bidirectional"))
    )
    (net (code "122") (name "unconnected-(U1-PD3_(INT1)-Pad12)") (class "Default")
      (node (ref "U1") (pin "12") (pinfunction "PD3_(INT1)_12") (pintype "bidirectional"))
    )
    (net (code "123") (name "unconnected-(U1-PD4_(OC1B)-Pad13)") (class "Default")
      (node (ref "U1") (pin "13") (pinfunction "PD4_(OC1B)_13") (pintype "bidirectional"))
    )
    (net (code "124") (name "unconnected-(U1-PD5_(OC1A)-Pad14)") (class "Default")
      (node (ref "U1") (pin "14") (pinfunction "PD5_(OC1A)_14") (pintype "bidirectional"))
    )
    (net (code "125") (name "unconnected-(U1-PD6_(ICP)-Pad15)") (class "Default")
      (node (ref "U1") (pin "15") (pinfunction "PD6_(ICP)_15") (pintype "bidirectional"))
    )
    (net (code "126") (name "unconnected-(U1-PD7_(OC2)-Pad16)") (class "Default")
      (node (ref "U1") (pin "16") (pinfunction "PD7_(OC2)_16") (pintype "bidirectional"))
    )
    (net (code "127") (name "unconnected-(U2-PA2_(ADC2{slash}AIN1{slash}PCINT2)-Pad11)") (class "Default")
      (node (ref "U2") (pin "11") (pinfunction "PA2_(ADC2/AIN1/PCINT2)_11") (pintype "bidirectional"))
    )
    (net (code "128") (name "unconnected-(U2-PA3_(ADC3{slash}T0{slash}PCINT3)-Pad10)") (class "Default")
      (node (ref "U2") (pin "10") (pinfunction "PA3_(ADC3/T0/PCINT3)_10") (pintype "bidirectional"))
    )
    (net (code "129") (name "unconnected-(U2-PA7_(PCINT7{slash}ICP{slash}OC0B{slash}ADC7)-Pad6)") (class "Default")
      (node (ref "U2") (pin "6") (pinfunction "PA7_(PCINT7/ICP/OC0B/ADC7)_6") (pintype "bidirectional"))
    )
    (net (code "130") (name "unconnected-(U3-PA2_(ADC2{slash}AIN1{slash}PCINT2)-Pad11)") (class "Default")
      (node (ref "U3") (pin "11") (pinfunction "PA2_(ADC2/AIN1/PCINT2)_11") (pintype "bidirectional"))
    )
    (net (code "131") (name "unconnected-(U3-PA3_(ADC3{slash}T0{slash}PCINT3)-Pad10)") (class "Default")
      (node (ref "U3") (pin "10") (pinfunction "PA3_(ADC3/T0/PCINT3)_10") (pintype "bidirectional"))
    )
    (net (code "132") (name "unconnected-(U3-PA7_(PCINT7{slash}ICP{slash}OC0B{slash}ADC7)-Pad6)") (class "Default")
      (node (ref "U3") (pin "6") (pinfunction "PA7_(PCINT7/ICP/OC0B/ADC7)_6") (pintype "bidirectional"))
    )
    (net (code "133") (name "unconnected-(U4-PA2_(ADC2{slash}AIN1{slash}PCINT2)-Pad11)") (class "Default")
      (node (ref "U4") (pin "11") (pinfunction "PA2_(ADC2/AIN1/PCINT2)_11") (pintype "bidirectional"))
    )
    (net (code "134") (name "unconnected-(U4-PA3_(ADC3{slash}T0{slash}PCINT3)-Pad10)") (class "Default")
      (node (ref "U4") (pin "10") (pinfunction "PA3_(ADC3/T0/PCINT3)_10") (pintype "bidirectional"))
    )
    (net (code "135") (name "unconnected-(U4-PA7_(PCINT7{slash}ICP{slash}OC0B{slash}ADC7)-Pad6)") (class "Default")
      (node (ref "U4") (pin "6") (pinfunction "PA7_(PCINT7/ICP/OC0B/ADC7)_6") (pintype "bidirectional"))
    )
    (net (code "136") (name "unconnected-(U5-PA2_(ADC2{slash}AIN1{slash}PCINT2)-Pad11)") (class "Default")
      (node (ref "U5") (pin "11") (pinfunction "PA2_(ADC2/AIN1/PCINT2)_11") (pintype "bidirectional"))
    )
    (net (code "137") (name "unconnected-(U5-PA3_(ADC3{slash}T0{slash}PCINT3)-Pad10)") (class "Default")
      (node (ref "U5") (pin "10") (pinfunction "PA3_(ADC3/T0/PCINT3)_10") (pintype "bidirectional"))
    )
    (net (code "138") (name "unconnected-(U5-PA7_(PCINT7{slash}ICP{slash}OC0B{slash}ADC7)-Pad6)") (class "Default")
      (node (ref "U5") (pin "6") (pinfunction "PA7_(PCINT7/ICP/OC0B/ADC7)_6") (pintype "bidirectional"))
    )
    (net (code "139") (name "unconnected-(U6-PA2_(ADC2{slash}AIN1{slash}PCINT2)-Pad11)") (class "Default")
      (node (ref "U6") (pin "11") (pinfunction "PA2_(ADC2/AIN1/PCINT2)_11") (pintype "bidirectional"))
    )
    (net (code "140") (name "unconnected-(U6-PA3_(ADC3{slash}T0{slash}PCINT3)-Pad10)") (class "Default")
      (node (ref "U6") (pin "10") (pinfunction "PA3_(ADC3/T0/PCINT3)_10") (pintype "bidirectional"))
    )
    (net (code "141") (name "unconnected-(U6-PA7_(PCINT7{slash}ICP{slash}OC0B{slash}ADC7)-Pad6)") (class "Default")
      (node (ref "U6") (pin "6") (pinfunction "PA7_(PCINT7/ICP/OC0B/ADC7)_6") (pintype "bidirectional"))
    )
    (net (code "142") (name "unconnected-(U10-AREF-Pad29)") (class "Default")
      (node (ref "U10") (pin "29") (pinfunction "AREF_29") (pintype "passive"))
    )
    (net (code "143") (name "unconnected-(U10-PA0_(ADC0)-Pad37)") (class "Default")
      (node (ref "U10") (pin "37") (pinfunction "PA0_(ADC0)_37") (pintype "bidirectional"))
    )
    (net (code "144") (name "unconnected-(U10-PA1_(ADC1)-Pad36)") (class "Default")
      (node (ref "U10") (pin "36") (pinfunction "PA1_(ADC1)_36") (pintype "bidirectional"))
    )
    (net (code "145") (name "unconnected-(U10-PA2_(ADC2)-Pad35)") (class "Default")
      (node (ref "U10") (pin "35") (pinfunction "PA2_(ADC2)_35") (pintype "bidirectional"))
    )
    (net (code "146") (name "unconnected-(U10-PA3_(ADC3)-Pad34)") (class "Default")
      (node (ref "U10") (pin "34") (pinfunction "PA3_(ADC3)_34") (pintype "bidirectional"))
    )
    (net (code "147") (name "unconnected-(U10-PA4_(ADC4)-Pad33)") (class "Default")
      (node (ref "U10") (pin "33") (pinfunction "PA4_(ADC4)_33") (pintype "bidirectional"))
    )
    (net (code "148") (name "unconnected-(U10-PA5_(ADC5)-Pad32)") (class "Default")
      (node (ref "U10") (pin "32") (pinfunction "PA5_(ADC5)_32") (pintype "bidirectional"))
    )
    (net (code "149") (name "unconnected-(U10-PA6_(ADC6)-Pad31)") (class "Default")
      (node (ref "U10") (pin "31") (pinfunction "PA6_(ADC6)_31") (pintype "bidirectional"))
    )
    (net (code "150") (name "unconnected-(U10-PA7_(ADC7)-Pad30)") (class "Default")
      (node (ref "U10") (pin "30") (pinfunction "PA7_(ADC7)_30") (pintype "bidirectional"))
    )
    (net (code "151") (name "unconnected-(U10-PB0_(XCK{slash}T0)-Pad40)") (class "Default")
      (node (ref "U10") (pin "40") (pinfunction "PB0_(XCK/T0)_40") (pintype "bidirectional"))
    )
    (net (code "152") (name "unconnected-(U10-PB1_(T1)-Pad41)") (class "Default")
      (node (ref "U10") (pin "41") (pinfunction "PB1_(T1)_41") (pintype "bidirectional"))
    )
    (net (code "153") (name "unconnected-(U10-PB3_(AIN1{slash}OC0)-Pad43)") (class "Default")
      (node (ref "U10") (pin "43") (pinfunction "PB3_(AIN1/OC0)_43") (pintype "bidirectional"))
    )
    (net (code "154") (name "unconnected-(U10-PC0_(SCL)-Pad19)") (class "Default")
      (node (ref "U10") (pin "19") (pinfunction "PC0_(SCL)_19") (pintype "bidirectional"))
    )
    (net (code "155") (name "unconnected-(U10-PC1_(SDA)-Pad20)") (class "Default")
      (node (ref "U10") (pin "20") (pinfunction "PC1_(SDA)_20") (pintype "bidirectional"))
    )
    (net (code "156") (name "unconnected-(U10-PC2_(TCK)-Pad21)") (class "Default")
      (node (ref "U10") (pin "21") (pinfunction "PC2_(TCK)_21") (pintype "bidirectional"))
    )
    (net (code "157") (name "unconnected-(U10-PC3_(TMS)-Pad22)") (class "Default")
      (node (ref "U10") (pin "22") (pinfunction "PC3_(TMS)_22") (pintype "bidirectional"))
    )
    (net (code "158") (name "unconnected-(U10-PC4_(TDO)-Pad23)") (class "Default")
      (node (ref "U10") (pin "23") (pinfunction "PC4_(TDO)_23") (pintype "bidirectional"))
    )
    (net (code "159") (name "unconnected-(U10-PC5_(TDI)-Pad24)") (class "Default")
      (node (ref "U10") (pin "24") (pinfunction "PC5_(TDI)_24") (pintype "bidirectional"))
    )
    (net (code "160") (name "unconnected-(U10-PC6_(TOSC1)-Pad25)") (class "Default")
      (node (ref "U10") (pin "25") (pinfunction "PC6_(TOSC1)_25") (pintype "bidirectional"))
    )
    (net (code "161") (name "unconnected-(U10-PC7_(TOSC2)-Pad26)") (class "Default")
      (node (ref "U10") (pin "26") (pinfunction "PC7_(TOSC2)_26") (pintype "bidirectional"))
    )
    (net (code "162") (name "unconnected-(U10-PD3_(INT1)-Pad12)") (class "Default")
      (node (ref "U10") (pin "12") (pinfunction "PD3_(INT1)_12") (pintype "bidirectional"))
    )
    (net (code "163") (name "unconnected-(U11-SCK{slash}PB2-Pad7)") (class "Default")
      (node (ref "U11") (pin "7") (pinfunction "SCK/PB2_7") (pintype "bidirectional"))
    )
  )
)
